# tf330.net
KiCad netlist of a schematic drawn in EAGLE
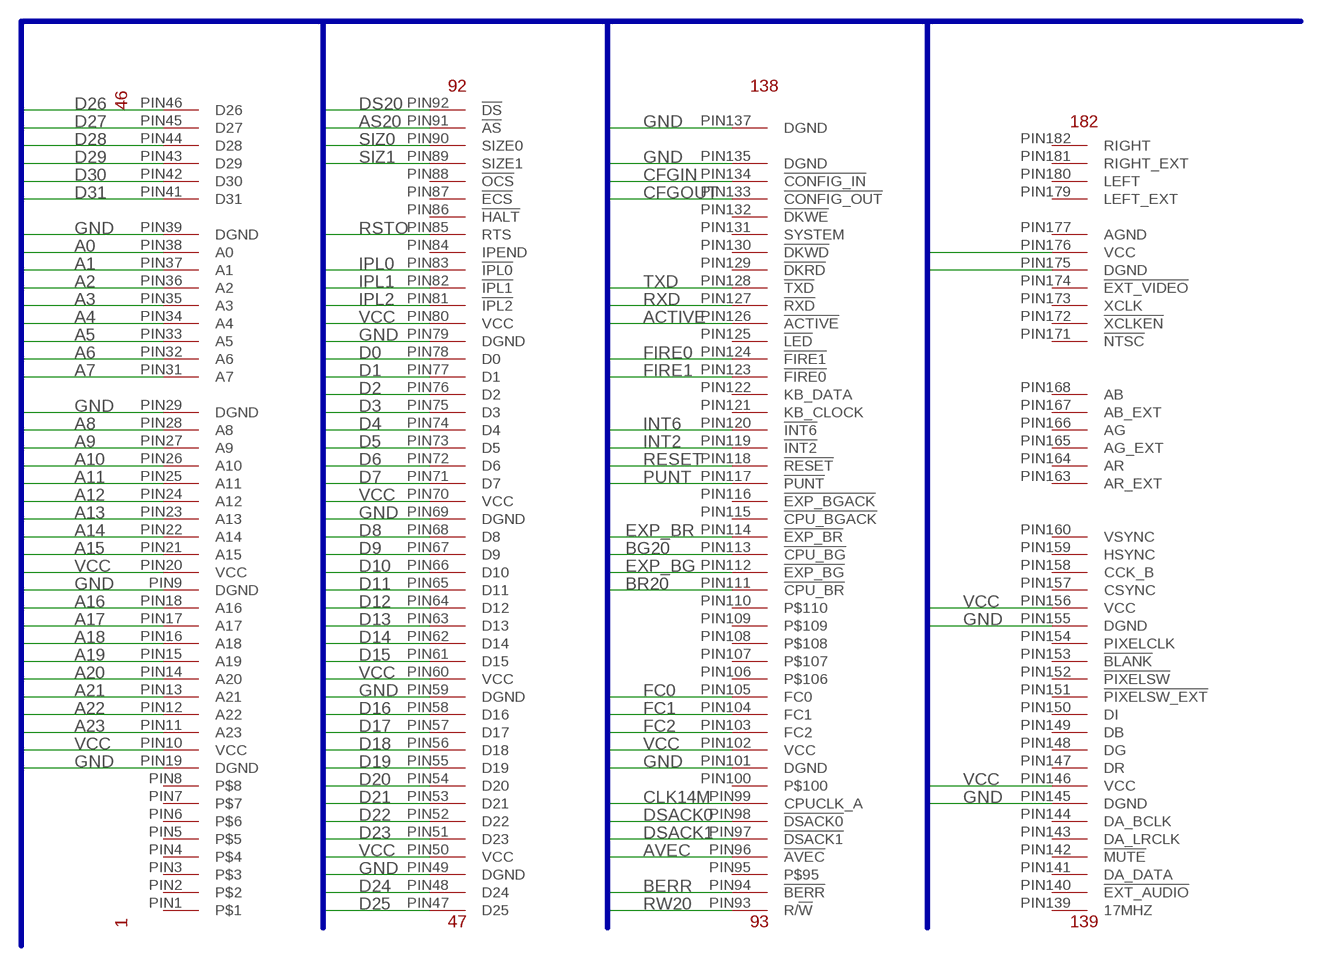
[diagram p0: schematic, sheet 1]
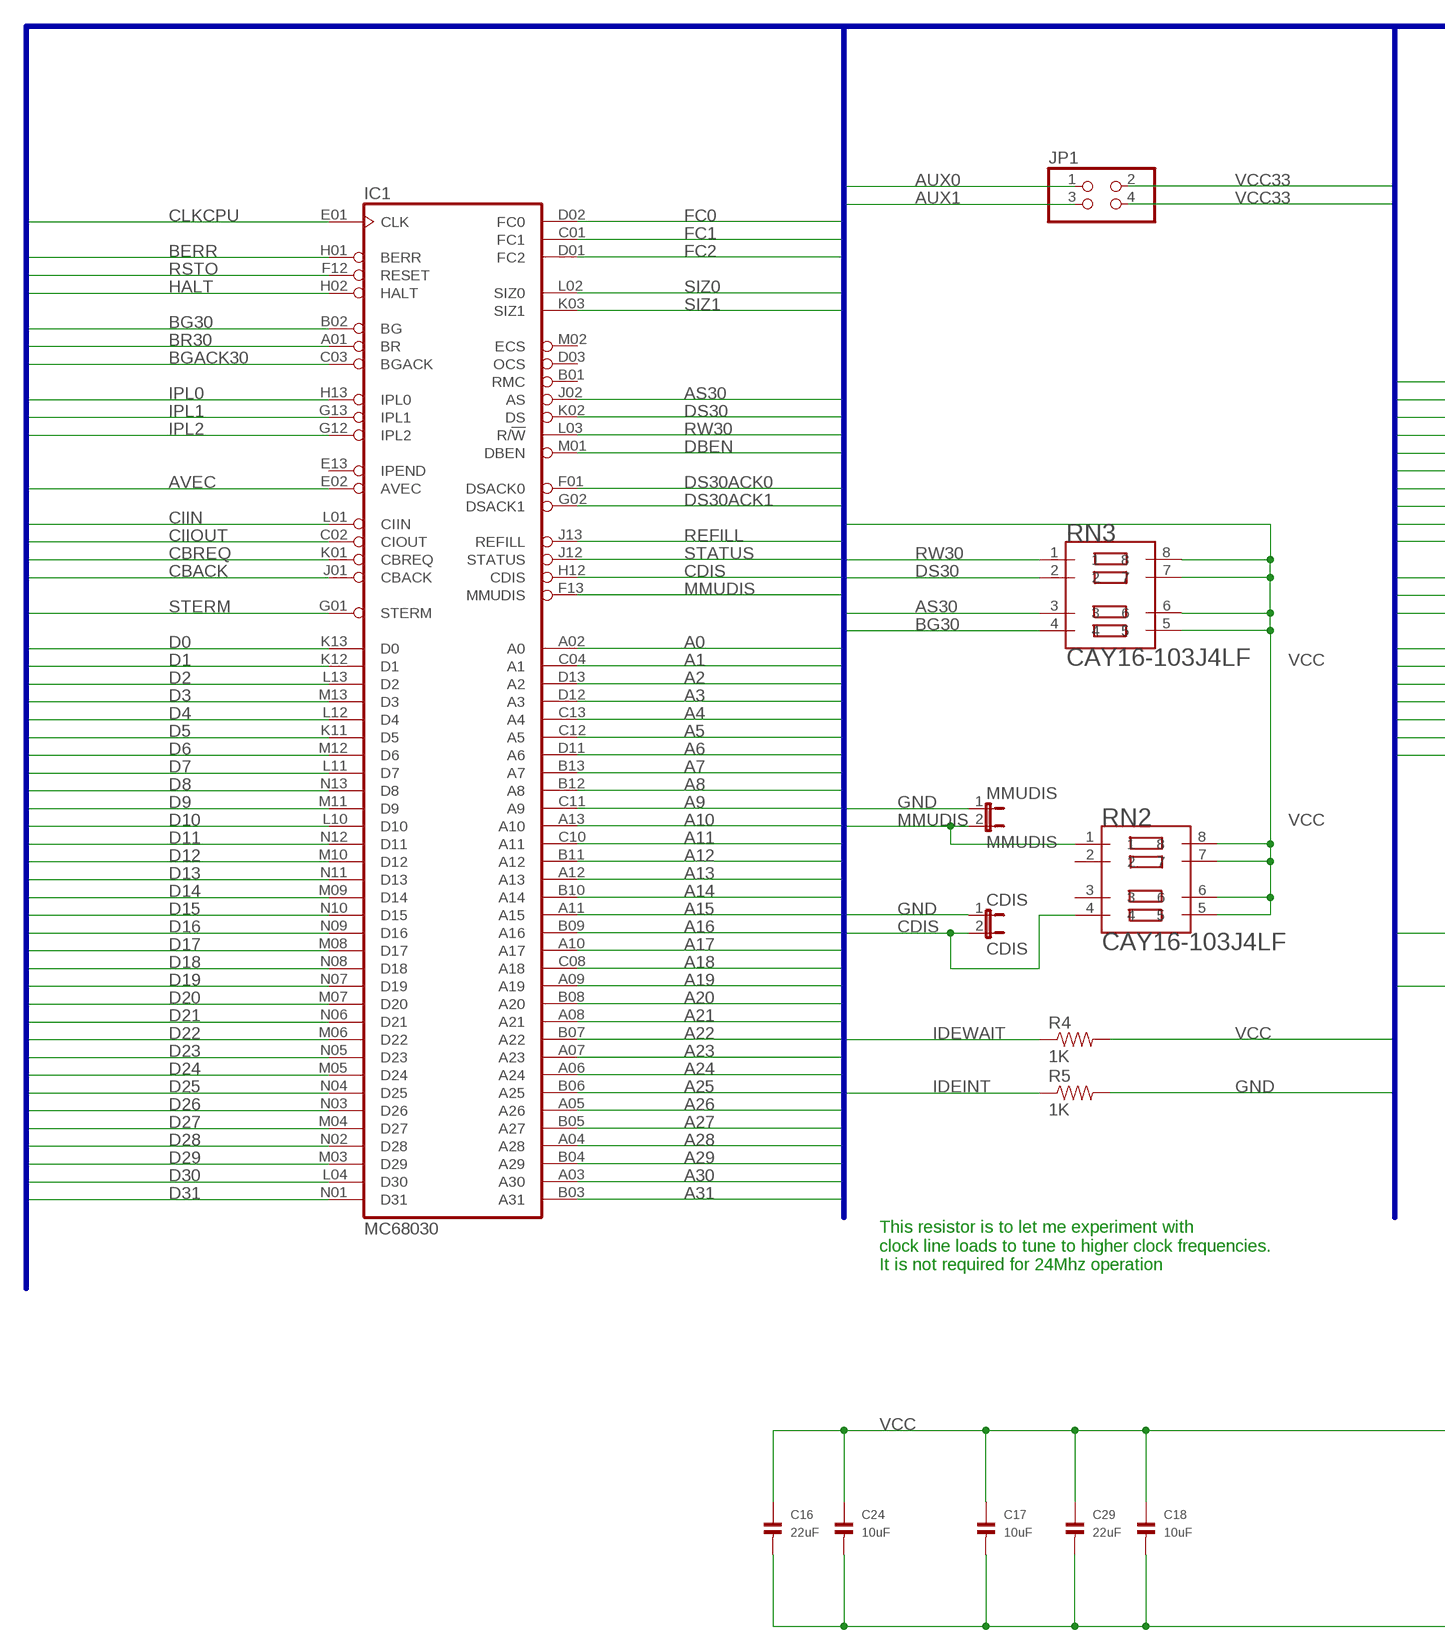
[diagram p1: schematic, sheet 2, part 1 of 2]
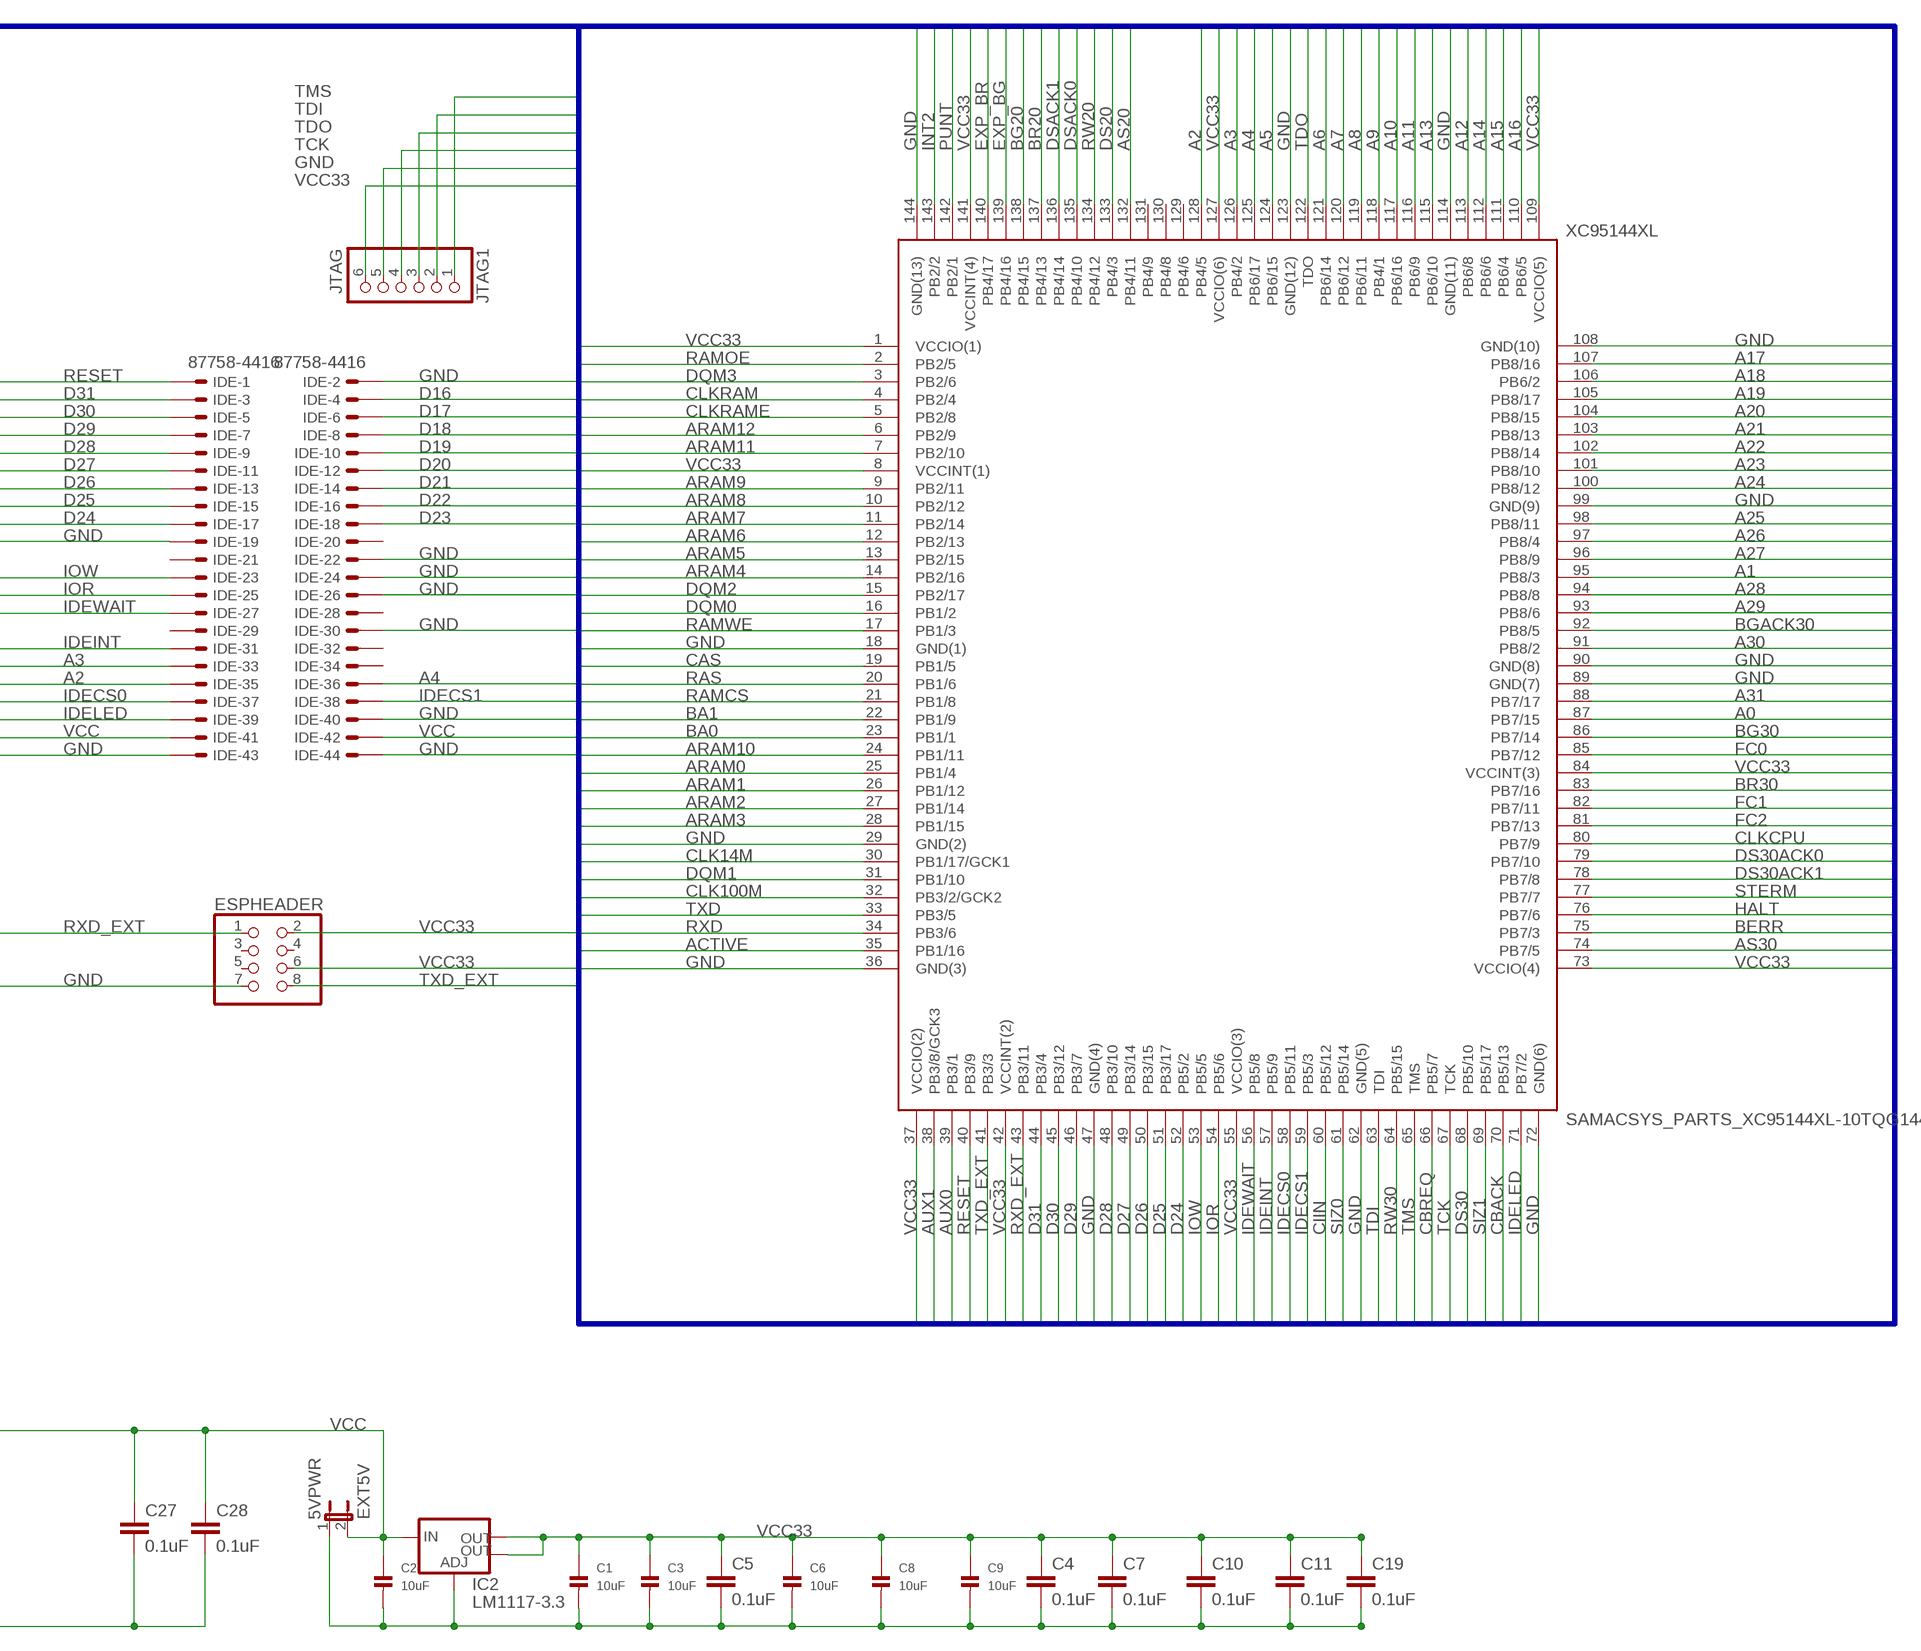
[diagram p2: schematic, sheet 2, part 2 of 2]
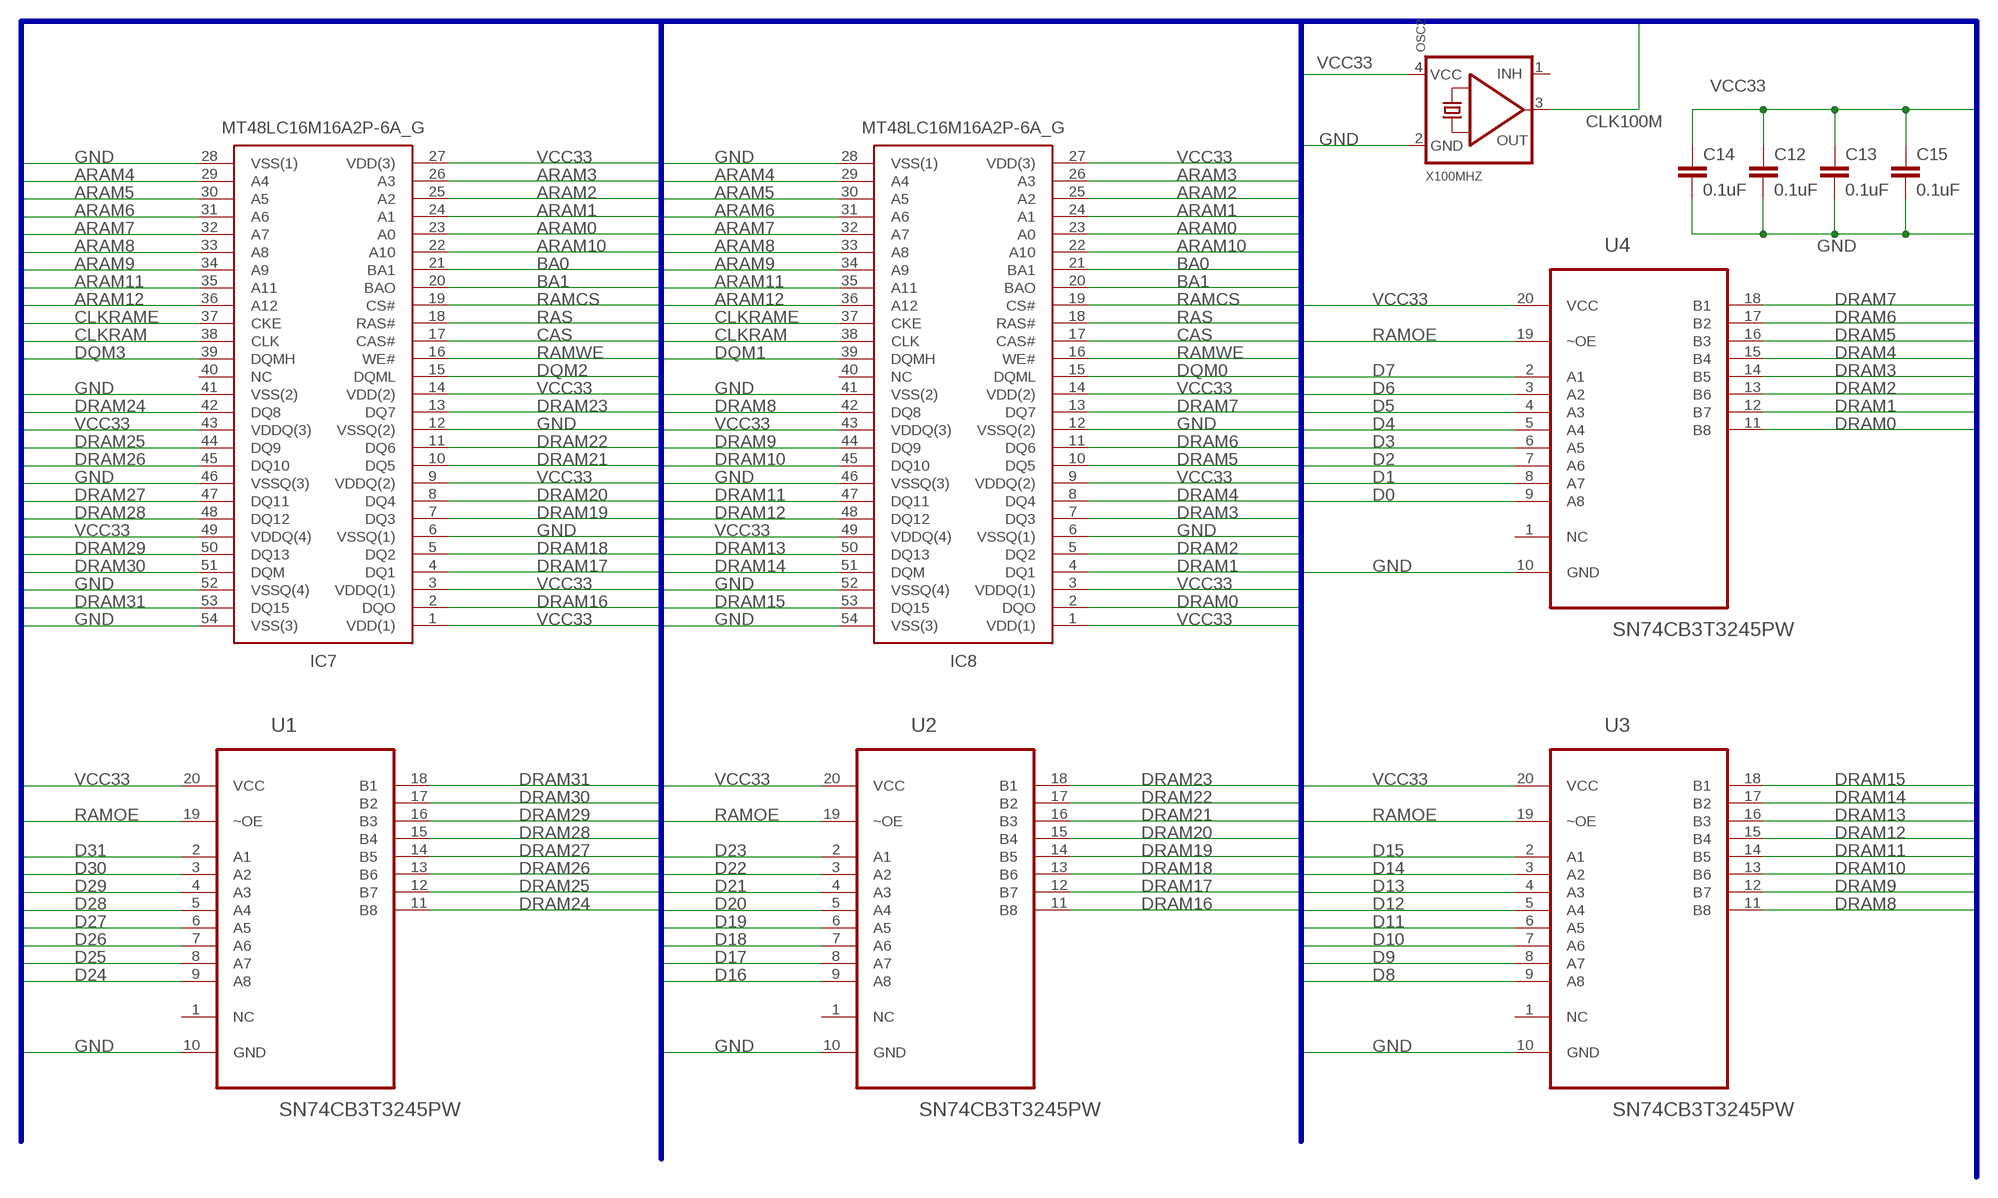
[diagram p3: schematic, sheet 3]

(export (version "E")
  (design (tool "Eeschema 10.0.6"))
  (components
    (comp (ref "CONN1")
      (value "MCA_CONN_182")
      (footprint "eagle-import:MCA_CONN_182")
      (libsource (lib "eagle-import") (part "MCA_CONN_182"))
    )
    (comp (ref "5VPWR")
      (value "EXT5V")
      (footprint "eagle-import:1X02")
      (libsource (lib "eagle-import") (part "JUMPER-2PTH"))
    )
    (comp (ref "C1")
      (value "10uF")
      (footprint "eagle-import:1206")
      (libsource (lib "eagle-import") (part "CAP_CERAMIC1206"))
    )
    (comp (ref "C2")
      (value "10uF")
      (footprint "eagle-import:1206")
      (libsource (lib "eagle-import") (part "CAP_CERAMIC1206"))
    )
    (comp (ref "C3")
      (value "10uF")
      (footprint "eagle-import:1206")
      (libsource (lib "eagle-import") (part "CAP_CERAMIC1206"))
    )
    (comp (ref "C4")
      (value "0.1uF")
      (footprint "eagle-import:0603-CAP")
      (libsource (lib "eagle-import") (part "0.1UF-25V(+80/-20%)(0603)"))
    )
    (comp (ref "C5")
      (value "0.1uF")
      (footprint "eagle-import:0603-CAP")
      (libsource (lib "eagle-import") (part "0.1UF-25V(+80/-20%)(0603)"))
    )
    (comp (ref "C6")
      (value "10uF")
      (footprint "eagle-import:1206")
      (libsource (lib "eagle-import") (part "CAP_CERAMIC1206"))
    )
    (comp (ref "C7")
      (value "0.1uF")
      (footprint "eagle-import:0603-CAP")
      (libsource (lib "eagle-import") (part "0.1UF-25V(+80/-20%)(0603)"))
    )
    (comp (ref "C8")
      (value "10uF")
      (footprint "eagle-import:1206")
      (libsource (lib "eagle-import") (part "CAP_CERAMIC1206"))
    )
    (comp (ref "C9")
      (value "10uF")
      (footprint "eagle-import:1206")
      (libsource (lib "eagle-import") (part "CAP_CERAMIC1206"))
    )
    (comp (ref "C10")
      (value "0.1uF")
      (footprint "eagle-import:0603-CAP")
      (libsource (lib "eagle-import") (part "0.1UF-25V(+80/-20%)(0603)"))
    )
    (comp (ref "C11")
      (value "0.1uF")
      (footprint "eagle-import:0603-CAP")
      (libsource (lib "eagle-import") (part "0.1UF-25V(+80/-20%)(0603)"))
    )
    (comp (ref "C16")
      (value "22uF")
      (footprint "eagle-import:1206")
      (libsource (lib "eagle-import") (part "CAP_CERAMIC1206"))
    )
    (comp (ref "C17")
      (value "10uF")
      (footprint "eagle-import:1206")
      (libsource (lib "eagle-import") (part "CAP_CERAMIC1206"))
    )
    (comp (ref "C18")
      (value "10uF")
      (footprint "eagle-import:1206")
      (libsource (lib "eagle-import") (part "CAP_CERAMIC1206"))
    )
    (comp (ref "C19")
      (value "0.1uF")
      (footprint "eagle-import:0603-CAP")
      (libsource (lib "eagle-import") (part "0.1UF-25V(+80/-20%)(0603)"))
    )
    (comp (ref "C24")
      (value "10uF")
      (footprint "eagle-import:1206")
      (libsource (lib "eagle-import") (part "CAP_CERAMIC1206"))
    )
    (comp (ref "C27")
      (value "0.1uF")
      (footprint "eagle-import:0603-CAP")
      (libsource (lib "eagle-import") (part "0.1UF-25V(+80/-20%)(0603)"))
    )
    (comp (ref "C28")
      (value "0.1uF")
      (footprint "eagle-import:0603-CAP")
      (libsource (lib "eagle-import") (part "0.1UF-25V(+80/-20%)(0603)"))
    )
    (comp (ref "C29")
      (value "22uF")
      (footprint "eagle-import:1206")
      (libsource (lib "eagle-import") (part "CAP_CERAMIC1206"))
    )
    (comp (ref "CDIS")
      (value "CDIS")
      (footprint "eagle-import:1X02")
      (libsource (lib "eagle-import") (part "JUMPER-2PTH"))
    )
    (comp (ref "ESPHEADER")
      (value "PINHD-2X4")
      (footprint "eagle-import:2X04")
      (libsource (lib "eagle-import") (part "PINHD-2X4"))
    )
    (comp (ref "IC1")
      (value "MC68030")
      (footprint "eagle-import:MPGA128")
      (fields (field (name "MF") "MOTOROLA") (field (name "MPN") "MC68030RC50C"))
      (libsource (lib "eagle-import") (part "MC68030RC"))
    )
    (comp (ref "IC2")
      (value "LM1117-3.3")
      (footprint "eagle-import:SOT223")
      (libsource (lib "eagle-import") (part "V_REG_LM1117SOT223"))
    )
    (comp (ref "IDE")
      (value "87758-4416")
      (footprint "eagle-import:87758-4416")
      (fields (field (name "MF") "MOLEX"))
      (libsource (lib "eagle-import") (part "87758-4416"))
    )
    (comp (ref "JP1")
      (value "PINHD-2X2")
      (footprint "eagle-import:2X02")
      (libsource (lib "eagle-import") (part "PINHD-2X2"))
    )
    (comp (ref "JTAG1")
      (value "JTAG")
      (footprint "eagle-import:1X06_ROUND")
      (libsource (lib "eagle-import") (part "HEADER-1X6ROUND"))
    )
    (comp (ref "MMUDIS")
      (value "MMUDIS")
      (footprint "eagle-import:1X02")
      (libsource (lib "eagle-import") (part "JUMPER-2PTH"))
    )
    (comp (ref "R4")
      (value "1K")
      (footprint "eagle-import:0603")
      (libsource (lib "eagle-import") (part "0.05OHM-1/5W-1%(0603)"))
    )
    (comp (ref "R5")
      (value "1K")
      (footprint "eagle-import:0603")
      (libsource (lib "eagle-import") (part "0.05OHM-1/5W-1%(0603)"))
    )
    (comp (ref "RN2")
      (value "CAY16-103J4LF")
      (footprint "eagle-import:RESCAXE80P320X160-8N")
      (fields (field (name "MF") "Bourns"))
      (libsource (lib "eagle-import") (part "CAY16-103J4LF"))
    )
    (comp (ref "RN3")
      (value "CAY16-103J4LF")
      (footprint "eagle-import:RESCAXE80P320X160-8N")
      (fields (field (name "MF") "Bourns"))
      (libsource (lib "eagle-import") (part "CAY16-103J4LF"))
    )
    (comp (ref "XC95144XL")
      (value "SAMACSYS_PARTS_XC95144XL-10TQG144I")
      (footprint "eagle-import:SAMACSYS_PARTS_QFP50P2200X2200X160-144N")
      (fields
        (field (name "MANUFACTURER_PART_NUMBER") "XC95144XL-10TQG144I")
        (field (name "RS_PART_NUMBER") "6260624")
      )
      (libsource (lib "eagle-import") (part "SAMACSYS_PARTS_XC95144XL-10TQG144I"))
    )
    (comp (ref "C12")
      (value "0.1uF")
      (footprint "eagle-import:0603-CAP")
      (libsource (lib "eagle-import") (part "0.1UF-25V(+80/-20%)(0603)"))
    )
    (comp (ref "C13")
      (value "0.1uF")
      (footprint "eagle-import:0603-CAP")
      (libsource (lib "eagle-import") (part "0.1UF-25V(+80/-20%)(0603)"))
    )
    (comp (ref "C14")
      (value "0.1uF")
      (footprint "eagle-import:0603-CAP")
      (libsource (lib "eagle-import") (part "0.1UF-25V(+80/-20%)(0603)"))
    )
    (comp (ref "C15")
      (value "0.1uF")
      (footprint "eagle-import:0603-CAP")
      (libsource (lib "eagle-import") (part "0.1UF-25V(+80/-20%)(0603)"))
    )
    (comp (ref "IC7")
      (value "MT48LC16M16A2P-6A_G")
      (footprint "eagle-import:SOP80P1176X120-54N")
      (fields
        (field (name "MANUFACTURER_PART_NUMBER") "MT48LC16M16A2P-6A:G")
        (field (name "RS_PART_NUMBER") "7824553")
      )
      (libsource (lib "eagle-import") (part "MT48LC16M16A2P-6A_G"))
    )
    (comp (ref "IC8")
      (value "MT48LC16M16A2P-6A_G")
      (footprint "eagle-import:SOP80P1176X120-54N")
      (fields
        (field (name "MANUFACTURER_PART_NUMBER") "MT48LC16M16A2P-6A:G")
        (field (name "RS_PART_NUMBER") "7824553")
      )
      (libsource (lib "eagle-import") (part "MT48LC16M16A2P-6A_G"))
    )
    (comp (ref "OSC2")
      (value "X100MHZ")
      (footprint "eagle-import:OSC_7X5MM")
      (libsource (lib "eagle-import") (part "OSCILLATOR"))
    )
    (comp (ref "U1")
      (value "SN74CB3T3245PW")
      (footprint "eagle-import:SOP65P640X120-20N")
      (fields (field (name "MF") "Texas Instruments"))
      (libsource (lib "eagle-import") (part "SN74CB3T3245PW"))
    )
    (comp (ref "U2")
      (value "SN74CB3T3245PW")
      (footprint "eagle-import:SOP65P640X120-20N")
      (fields (field (name "MF") "Texas Instruments"))
      (libsource (lib "eagle-import") (part "SN74CB3T3245PW"))
    )
    (comp (ref "U3")
      (value "SN74CB3T3245PW")
      (footprint "eagle-import:SOP65P640X120-20N")
      (fields (field (name "MF") "Texas Instruments"))
      (libsource (lib "eagle-import") (part "SN74CB3T3245PW"))
    )
    (comp (ref "U4")
      (value "SN74CB3T3245PW")
      (footprint "eagle-import:SOP65P640X120-20N")
      (fields (field (name "MF") "Texas Instruments"))
      (libsource (lib "eagle-import") (part "SN74CB3T3245PW"))
    )
  )
  (nets
    (net (code "11") (name "A0") (class "Default")
      (node (ref "CONN1") (pin "PIN38") (pinfunction "A0_PIN38") (pintype "bidirectional"))
      (node (ref "IC1") (pin "A02") (pinfunction "A0_A02") (pintype "output"))
      (node (ref "XC95144XL") (pin "87") (pinfunction "PB7/15_87") (pintype "input"))
    )
    (net (code "12") (name "A1") (class "Default")
      (node (ref "CONN1") (pin "PIN37") (pinfunction "A1_PIN37") (pintype "bidirectional"))
      (node (ref "IC1") (pin "C04") (pinfunction "A1_C04") (pintype "output"))
      (node (ref "XC95144XL") (pin "95") (pinfunction "PB8/3_95") (pintype "input"))
    )
    (net (code "13") (name "A2") (class "Default")
      (node (ref "CONN1") (pin "PIN36") (pinfunction "A2_PIN36") (pintype "bidirectional"))
      (node (ref "IC1") (pin "D13") (pinfunction "A2_D13") (pintype "output"))
      (node (ref "IDE") (pin "35") (pinfunction "S_35") (pintype "passive"))
      (node (ref "XC95144XL") (pin "128") (pinfunction "PB4/5_128") (pintype "input"))
    )
    (net (code "14") (name "A3") (class "Default")
      (node (ref "CONN1") (pin "PIN35") (pinfunction "A3_PIN35") (pintype "bidirectional"))
      (node (ref "IC1") (pin "D12") (pinfunction "A3_D12") (pintype "output"))
      (node (ref "IDE") (pin "33") (pinfunction "S_33") (pintype "passive"))
      (node (ref "XC95144XL") (pin "126") (pinfunction "PB4/2_126") (pintype "input"))
    )
    (net (code "15") (name "A4") (class "Default")
      (node (ref "CONN1") (pin "PIN34") (pinfunction "A4_PIN34") (pintype "bidirectional"))
      (node (ref "IC1") (pin "C13") (pinfunction "A4_C13") (pintype "output"))
      (node (ref "IDE") (pin "36") (pinfunction "S_36") (pintype "passive"))
      (node (ref "XC95144XL") (pin "125") (pinfunction "PB6/17_125") (pintype "input"))
    )
    (net (code "16") (name "A5") (class "Default")
      (node (ref "CONN1") (pin "PIN33") (pinfunction "A5_PIN33") (pintype "bidirectional"))
      (node (ref "IC1") (pin "C12") (pinfunction "A5_C12") (pintype "output"))
      (node (ref "XC95144XL") (pin "124") (pinfunction "PB6/15_124") (pintype "input"))
    )
    (net (code "17") (name "A6") (class "Default")
      (node (ref "CONN1") (pin "PIN32") (pinfunction "A6_PIN32") (pintype "bidirectional"))
      (node (ref "IC1") (pin "D11") (pinfunction "A6_D11") (pintype "output"))
      (node (ref "XC95144XL") (pin "121") (pinfunction "PB6/14_121") (pintype "input"))
    )
    (net (code "18") (name "A7") (class "Default")
      (node (ref "CONN1") (pin "PIN31") (pinfunction "A7_PIN31") (pintype "bidirectional"))
      (node (ref "IC1") (pin "B13") (pinfunction "A7_B13") (pintype "output"))
      (node (ref "XC95144XL") (pin "120") (pinfunction "PB6/12_120") (pintype "input"))
    )
    (net (code "19") (name "A8") (class "Default")
      (node (ref "CONN1") (pin "PIN28") (pinfunction "A8_PIN28") (pintype "bidirectional"))
      (node (ref "IC1") (pin "B12") (pinfunction "A8_B12") (pintype "output"))
      (node (ref "XC95144XL") (pin "119") (pinfunction "PB6/11_119") (pintype "input"))
    )
    (net (code "20") (name "A9") (class "Default")
      (node (ref "CONN1") (pin "PIN27") (pinfunction "A9_PIN27") (pintype "bidirectional"))
      (node (ref "IC1") (pin "C11") (pinfunction "A9_C11") (pintype "output"))
      (node (ref "XC95144XL") (pin "118") (pinfunction "PB4/1_118") (pintype "input"))
    )
    (net (code "21") (name "A10") (class "Default")
      (node (ref "CONN1") (pin "PIN26") (pinfunction "A10_PIN26") (pintype "bidirectional"))
      (node (ref "IC1") (pin "A13") (pinfunction "A10_A13") (pintype "output"))
      (node (ref "XC95144XL") (pin "117") (pinfunction "PB6/16_117") (pintype "input"))
    )
    (net (code "22") (name "A11") (class "Default")
      (node (ref "CONN1") (pin "PIN25") (pinfunction "A11_PIN25") (pintype "bidirectional"))
      (node (ref "IC1") (pin "C10") (pinfunction "A11_C10") (pintype "output"))
      (node (ref "XC95144XL") (pin "116") (pinfunction "PB6/9_116") (pintype "input"))
    )
    (net (code "23") (name "A12") (class "Default")
      (node (ref "CONN1") (pin "PIN24") (pinfunction "A12_PIN24") (pintype "bidirectional"))
      (node (ref "IC1") (pin "B11") (pinfunction "A12_B11") (pintype "output"))
      (node (ref "XC95144XL") (pin "113") (pinfunction "PB6/8_113") (pintype "input"))
    )
    (net (code "24") (name "A13") (class "Default")
      (node (ref "CONN1") (pin "PIN23") (pinfunction "A13_PIN23") (pintype "bidirectional"))
      (node (ref "IC1") (pin "A12") (pinfunction "A13_A12") (pintype "output"))
      (node (ref "XC95144XL") (pin "115") (pinfunction "PB6/10_115") (pintype "input"))
    )
    (net (code "25") (name "A14") (class "Default")
      (node (ref "CONN1") (pin "PIN22") (pinfunction "A14_PIN22") (pintype "bidirectional"))
      (node (ref "IC1") (pin "B10") (pinfunction "A14_B10") (pintype "output"))
      (node (ref "XC95144XL") (pin "112") (pinfunction "PB6/6_112") (pintype "input"))
    )
    (net (code "26") (name "A15") (class "Default")
      (node (ref "CONN1") (pin "PIN21") (pinfunction "A15_PIN21") (pintype "bidirectional"))
      (node (ref "IC1") (pin "A11") (pinfunction "A15_A11") (pintype "output"))
      (node (ref "XC95144XL") (pin "111") (pinfunction "PB6/4_111") (pintype "input"))
    )
    (net (code "27") (name "A16") (class "Default")
      (node (ref "CONN1") (pin "PIN18") (pinfunction "A16_PIN18") (pintype "bidirectional"))
      (node (ref "IC1") (pin "B09") (pinfunction "A16_B09") (pintype "output"))
      (node (ref "XC95144XL") (pin "110") (pinfunction "PB6/5_110") (pintype "input"))
    )
    (net (code "28") (name "A17") (class "Default")
      (node (ref "CONN1") (pin "PIN17") (pinfunction "A17_PIN17") (pintype "bidirectional"))
      (node (ref "IC1") (pin "A10") (pinfunction "A17_A10") (pintype "output"))
      (node (ref "XC95144XL") (pin "107") (pinfunction "PB8/16_107") (pintype "input"))
    )
    (net (code "29") (name "A18") (class "Default")
      (node (ref "CONN1") (pin "PIN16") (pinfunction "A18_PIN16") (pintype "bidirectional"))
      (node (ref "IC1") (pin "C08") (pinfunction "A18_C08") (pintype "output"))
      (node (ref "XC95144XL") (pin "106") (pinfunction "PB6/2_106") (pintype "input"))
    )
    (net (code "30") (name "A19") (class "Default")
      (node (ref "CONN1") (pin "PIN15") (pinfunction "A19_PIN15") (pintype "bidirectional"))
      (node (ref "IC1") (pin "A09") (pinfunction "A19_A09") (pintype "output"))
      (node (ref "XC95144XL") (pin "105") (pinfunction "PB8/17_105") (pintype "input"))
    )
    (net (code "31") (name "A20") (class "Default")
      (node (ref "CONN1") (pin "PIN14") (pinfunction "A20_PIN14") (pintype "bidirectional"))
      (node (ref "IC1") (pin "B08") (pinfunction "A20_B08") (pintype "output"))
      (node (ref "XC95144XL") (pin "104") (pinfunction "PB8/15_104") (pintype "input"))
    )
    (net (code "32") (name "A21") (class "Default")
      (node (ref "CONN1") (pin "PIN13") (pinfunction "A21_PIN13") (pintype "bidirectional"))
      (node (ref "IC1") (pin "A08") (pinfunction "A21_A08") (pintype "output"))
      (node (ref "XC95144XL") (pin "103") (pinfunction "PB8/13_103") (pintype "input"))
    )
    (net (code "33") (name "A22") (class "Default")
      (node (ref "CONN1") (pin "PIN12") (pinfunction "A22_PIN12") (pintype "bidirectional"))
      (node (ref "IC1") (pin "B07") (pinfunction "A22_B07") (pintype "output"))
      (node (ref "XC95144XL") (pin "102") (pinfunction "PB8/14_102") (pintype "input"))
    )
    (net (code "34") (name "A23") (class "Default")
      (node (ref "CONN1") (pin "PIN11") (pinfunction "A23_PIN11") (pintype "bidirectional"))
      (node (ref "IC1") (pin "A07") (pinfunction "A23_A07") (pintype "output"))
      (node (ref "XC95144XL") (pin "101") (pinfunction "PB8/10_101") (pintype "input"))
    )
    (net (code "35") (name "A24") (class "Default")
      (node (ref "IC1") (pin "A06") (pinfunction "A24_A06") (pintype "output"))
      (node (ref "XC95144XL") (pin "100") (pinfunction "PB8/12_100") (pintype "input"))
    )
    (net (code "36") (name "A25") (class "Default")
      (node (ref "IC1") (pin "B06") (pinfunction "A25_B06") (pintype "output"))
      (node (ref "XC95144XL") (pin "98") (pinfunction "PB8/11_98") (pintype "input"))
    )
    (net (code "37") (name "A26") (class "Default")
      (node (ref "IC1") (pin "A05") (pinfunction "A26_A05") (pintype "output"))
      (node (ref "XC95144XL") (pin "97") (pinfunction "PB8/4_97") (pintype "input"))
    )
    (net (code "38") (name "A27") (class "Default")
      (node (ref "IC1") (pin "B05") (pinfunction "A27_B05") (pintype "output"))
      (node (ref "XC95144XL") (pin "96") (pinfunction "PB8/9_96") (pintype "input"))
    )
    (net (code "39") (name "A28") (class "Default")
      (node (ref "IC1") (pin "A04") (pinfunction "A28_A04") (pintype "output"))
      (node (ref "XC95144XL") (pin "94") (pinfunction "PB8/8_94") (pintype "input"))
    )
    (net (code "40") (name "A29") (class "Default")
      (node (ref "IC1") (pin "B04") (pinfunction "A29_B04") (pintype "output"))
      (node (ref "XC95144XL") (pin "93") (pinfunction "PB8/6_93") (pintype "input"))
    )
    (net (code "41") (name "A30") (class "Default")
      (node (ref "IC1") (pin "A03") (pinfunction "A30_A03") (pintype "output"))
      (node (ref "XC95144XL") (pin "91") (pinfunction "PB8/2_91") (pintype "input"))
    )
    (net (code "42") (name "A31") (class "Default")
      (node (ref "IC1") (pin "B03") (pinfunction "A31_B03") (pintype "output"))
      (node (ref "XC95144XL") (pin "88") (pinfunction "PB7/17_88") (pintype "input"))
    )
    (net (code "43") (name "ACTIVE") (class "Default")
      (node (ref "CONN1") (pin "PIN126") (pinfunction "~{ACTIVE}_PIN126") (pintype "bidirectional"))
      (node (ref "XC95144XL") (pin "35") (pinfunction "PB1/16_35") (pintype "input"))
    )
    (net (code "44") (name "AGND") (class "Default")
      (node (ref "CONN1") (pin "PIN177") (pinfunction "AGND_PIN177") (pintype "power_in"))
    )
    (net (code "45") (name "ARAM0") (class "Default")
      (node (ref "IC7") (pin "23") (pinfunction "A0_23") (pintype "input"))
      (node (ref "IC8") (pin "23") (pinfunction "A0_23") (pintype "input"))
      (node (ref "XC95144XL") (pin "25") (pinfunction "PB1/4_25") (pintype "input"))
    )
    (net (code "46") (name "ARAM1") (class "Default")
      (node (ref "IC7") (pin "24") (pinfunction "A1_24") (pintype "input"))
      (node (ref "IC8") (pin "24") (pinfunction "A1_24") (pintype "input"))
      (node (ref "XC95144XL") (pin "26") (pinfunction "PB1/12_26") (pintype "input"))
    )
    (net (code "47") (name "ARAM2") (class "Default")
      (node (ref "IC7") (pin "25") (pinfunction "A2_25") (pintype "input"))
      (node (ref "IC8") (pin "25") (pinfunction "A2_25") (pintype "input"))
      (node (ref "XC95144XL") (pin "27") (pinfunction "PB1/14_27") (pintype "input"))
    )
    (net (code "48") (name "ARAM3") (class "Default")
      (node (ref "IC7") (pin "26") (pinfunction "A3_26") (pintype "input"))
      (node (ref "IC8") (pin "26") (pinfunction "A3_26") (pintype "input"))
      (node (ref "XC95144XL") (pin "28") (pinfunction "PB1/15_28") (pintype "input"))
    )
    (net (code "49") (name "ARAM4") (class "Default")
      (node (ref "IC7") (pin "29") (pinfunction "A4_29") (pintype "input"))
      (node (ref "IC8") (pin "29") (pinfunction "A4_29") (pintype "input"))
      (node (ref "XC95144XL") (pin "14") (pinfunction "PB2/16_14") (pintype "input"))
    )
    (net (code "50") (name "ARAM5") (class "Default")
      (node (ref "IC7") (pin "30") (pinfunction "A5_30") (pintype "input"))
      (node (ref "IC8") (pin "30") (pinfunction "A5_30") (pintype "input"))
      (node (ref "XC95144XL") (pin "13") (pinfunction "PB2/15_13") (pintype "input"))
    )
    (net (code "51") (name "ARAM6") (class "Default")
      (node (ref "IC7") (pin "31") (pinfunction "A6_31") (pintype "input"))
      (node (ref "IC8") (pin "31") (pinfunction "A6_31") (pintype "input"))
      (node (ref "XC95144XL") (pin "12") (pinfunction "PB2/13_12") (pintype "input"))
    )
    (net (code "52") (name "ARAM7") (class "Default")
      (node (ref "IC7") (pin "32") (pinfunction "A7_32") (pintype "input"))
      (node (ref "IC8") (pin "32") (pinfunction "A7_32") (pintype "input"))
      (node (ref "XC95144XL") (pin "11") (pinfunction "PB2/14_11") (pintype "input"))
    )
    (net (code "53") (name "ARAM8") (class "Default")
      (node (ref "IC7") (pin "33") (pinfunction "A8_33") (pintype "input"))
      (node (ref "IC8") (pin "33") (pinfunction "A8_33") (pintype "input"))
      (node (ref "XC95144XL") (pin "10") (pinfunction "PB2/12_10") (pintype "input"))
    )
    (net (code "54") (name "ARAM9") (class "Default")
      (node (ref "IC7") (pin "34") (pinfunction "A9_34") (pintype "input"))
      (node (ref "IC8") (pin "34") (pinfunction "A9_34") (pintype "input"))
      (node (ref "XC95144XL") (pin "9") (pinfunction "PB2/11_9") (pintype "input"))
    )
    (net (code "55") (name "ARAM10") (class "Default")
      (node (ref "IC7") (pin "22") (pinfunction "A10_22") (pintype "input"))
      (node (ref "IC8") (pin "22") (pinfunction "A10_22") (pintype "input"))
      (node (ref "XC95144XL") (pin "24") (pinfunction "PB1/11_24") (pintype "input"))
    )
    (net (code "56") (name "ARAM11") (class "Default")
      (node (ref "IC7") (pin "35") (pinfunction "A11_35") (pintype "input"))
      (node (ref "IC8") (pin "35") (pinfunction "A11_35") (pintype "input"))
      (node (ref "XC95144XL") (pin "7") (pinfunction "PB2/10_7") (pintype "input"))
    )
    (net (code "57") (name "ARAM12") (class "Default")
      (node (ref "IC7") (pin "36") (pinfunction "A12_36") (pintype "input"))
      (node (ref "IC8") (pin "36") (pinfunction "A12_36") (pintype "input"))
      (node (ref "XC95144XL") (pin "6") (pinfunction "PB2/9_6") (pintype "input"))
    )
    (net (code "58") (name "AS20") (class "Default")
      (node (ref "CONN1") (pin "PIN91") (pinfunction "~{AS}_PIN91") (pintype "bidirectional"))
      (node (ref "XC95144XL") (pin "132") (pinfunction "PB4/11_132") (pintype "input"))
    )
    (net (code "59") (name "AS30") (class "Default")
      (node (ref "IC1") (pin "J02") (pinfunction "AS_J02") (pintype "output"))
      (node (ref "RN3") (pin "3") (pinfunction "3_3") (pintype "passive"))
      (node (ref "XC95144XL") (pin "74") (pinfunction "PB7/5_74") (pintype "input"))
    )
    (net (code "60") (name "AUX0") (class "Default")
      (node (ref "JP1") (pin "1") (pinfunction "1_1") (pintype "passive"))
      (node (ref "XC95144XL") (pin "39") (pinfunction "PB3/1_39") (pintype "input"))
    )
    (net (code "61") (name "AUX1") (class "Default")
      (node (ref "JP1") (pin "3") (pinfunction "3_3") (pintype "passive"))
      (node (ref "XC95144XL") (pin "38") (pinfunction "PB3/8/GCK3_38") (pintype "input"))
    )
    (net (code "62") (name "AVEC") (class "Default")
      (node (ref "CONN1") (pin "PIN96") (pinfunction "~{AVEC}_PIN96") (pintype "bidirectional"))
      (node (ref "IC1") (pin "E02") (pinfunction "AVEC_E02") (pintype "input"))
    )
    (net (code "63") (name "BA0") (class "Default")
      (node (ref "IC7") (pin "21") (pinfunction "BA1_21") (pintype "input"))
      (node (ref "IC8") (pin "21") (pinfunction "BA1_21") (pintype "input"))
      (node (ref "XC95144XL") (pin "23") (pinfunction "PB1/1_23") (pintype "input"))
    )
    (net (code "64") (name "BA1") (class "Default")
      (node (ref "IC7") (pin "20") (pinfunction "BAO_20") (pintype "input"))
      (node (ref "IC8") (pin "20") (pinfunction "BAO_20") (pintype "input"))
      (node (ref "XC95144XL") (pin "22") (pinfunction "PB1/9_22") (pintype "input"))
    )
    (net (code "65") (name "BERR") (class "Default")
      (node (ref "CONN1") (pin "PIN94") (pinfunction "~{BERR}_PIN94") (pintype "bidirectional"))
      (node (ref "IC1") (pin "H01") (pinfunction "BERR_H01") (pintype "input"))
      (node (ref "XC95144XL") (pin "75") (pinfunction "PB7/3_75") (pintype "input"))
    )
    (net (code "66") (name "BG20") (class "Default")
      (node (ref "CONN1") (pin "PIN113") (pinfunction "~{CPU_BG}_PIN113") (pintype "bidirectional"))
      (node (ref "XC95144XL") (pin "138") (pinfunction "PB4/15_138") (pintype "input"))
    )
    (net (code "67") (name "BG30") (class "Default")
      (node (ref "IC1") (pin "B02") (pinfunction "BG_B02") (pintype "output"))
      (node (ref "RN3") (pin "4") (pinfunction "4_4") (pintype "passive"))
      (node (ref "XC95144XL") (pin "86") (pinfunction "PB7/14_86") (pintype "input"))
    )
    (net (code "68") (name "BGACK30") (class "Default")
      (node (ref "IC1") (pin "C03") (pinfunction "BGACK_C03") (pintype "input"))
      (node (ref "XC95144XL") (pin "92") (pinfunction "PB8/5_92") (pintype "input"))
    )
    (net (code "69") (name "BR20") (class "Default")
      (node (ref "CONN1") (pin "PIN111") (pinfunction "~{CPU_BR}_PIN111") (pintype "bidirectional"))
      (node (ref "XC95144XL") (pin "137") (pinfunction "PB4/13_137") (pintype "input"))
    )
    (net (code "70") (name "BR30") (class "Default")
      (node (ref "IC1") (pin "A01") (pinfunction "BR_A01") (pintype "input"))
      (node (ref "XC95144XL") (pin "83") (pinfunction "PB7/16_83") (pintype "input"))
    )
    (net (code "71") (name "CAS") (class "Default")
      (node (ref "IC7") (pin "17") (pinfunction "CAS#_17") (pintype "input"))
      (node (ref "IC8") (pin "17") (pinfunction "CAS#_17") (pintype "input"))
      (node (ref "XC95144XL") (pin "19") (pinfunction "PB1/5_19") (pintype "input"))
    )
    (net (code "72") (name "CBACK") (class "Default")
      (node (ref "IC1") (pin "J01") (pinfunction "CBACK_J01") (pintype "input"))
      (node (ref "XC95144XL") (pin "70") (pinfunction "PB5/13_70") (pintype "input"))
    )
    (net (code "73") (name "CBREQ") (class "Default")
      (node (ref "IC1") (pin "K01") (pinfunction "CBREQ_K01") (pintype "output"))
      (node (ref "XC95144XL") (pin "66") (pinfunction "PB5/7_66") (pintype "input"))
    )
    (net (code "74") (name "CDIS") (class "Default")
      (node (ref "CDIS") (pin "2") (pinfunction "2_2") (pintype "passive"))
      (node (ref "IC1") (pin "H12") (pinfunction "CDIS_H12") (pintype "input"))
      (node (ref "RN2") (pin "4") (pinfunction "4_4") (pintype "passive"))
    )
    (net (code "75") (name "CFGIN") (class "Default")
      (node (ref "CONN1") (pin "PIN134") (pinfunction "~{CONFIG_IN}_PIN134") (pintype "bidirectional"))
    )
    (net (code "76") (name "CFGOUT") (class "Default")
      (node (ref "CONN1") (pin "PIN133") (pinfunction "~{CONFIG_OUT}_PIN133") (pintype "bidirectional"))
    )
    (net (code "77") (name "CIIN") (class "Default")
      (node (ref "IC1") (pin "L01") (pinfunction "CIIN_L01") (pintype "input"))
      (node (ref "XC95144XL") (pin "60") (pinfunction "PB5/12_60") (pintype "input"))
    )
    (net (code "78") (name "CIIOUT") (class "Default")
      (node (ref "IC1") (pin "C02") (pinfunction "CIOUT_C02") (pintype "output"))
    )
    (net (code "79") (name "CLK14M") (class "Default")
      (node (ref "CONN1") (pin "PIN99") (pinfunction "CPUCLK_A_PIN99") (pintype "bidirectional"))
      (node (ref "XC95144XL") (pin "30") (pinfunction "PB1/17/GCK1_30") (pintype "input"))
    )
    (net (code "80") (name "CLK100M") (class "Default")
      (node (ref "OSC2") (pin "3") (pinfunction "OUT_3") (pintype "output"))
      (node (ref "XC95144XL") (pin "32") (pinfunction "PB3/2/GCK2_32") (pintype "input"))
    )
    (net (code "81") (name "CLKCPU") (class "Default")
      (node (ref "IC1") (pin "E01") (pinfunction "CLK_E01") (pintype "input"))
      (node (ref "XC95144XL") (pin "80") (pinfunction "PB7/9_80") (pintype "input"))
    )
    (net (code "82") (name "CLKRAM") (class "Default")
      (node (ref "IC7") (pin "38") (pinfunction "CLK_38") (pintype "input"))
      (node (ref "IC8") (pin "38") (pinfunction "CLK_38") (pintype "input"))
      (node (ref "XC95144XL") (pin "4") (pinfunction "PB2/4_4") (pintype "input"))
    )
    (net (code "83") (name "CLKRAME") (class "Default")
      (node (ref "IC7") (pin "37") (pinfunction "CKE_37") (pintype "input"))
      (node (ref "IC8") (pin "37") (pinfunction "CKE_37") (pintype "input"))
      (node (ref "XC95144XL") (pin "5") (pinfunction "PB2/8_5") (pintype "input"))
    )
    (net (code "84") (name "D0") (class "Default")
      (node (ref "CONN1") (pin "PIN78") (pinfunction "D0_PIN78") (pintype "bidirectional"))
      (node (ref "IC1") (pin "K13") (pinfunction "D0_K13") (pintype "bidirectional"))
      (node (ref "U4") (pin "9") (pinfunction "A8_9") (pintype "bidirectional"))
    )
    (net (code "85") (name "D1") (class "Default")
      (node (ref "CONN1") (pin "PIN77") (pinfunction "D1_PIN77") (pintype "bidirectional"))
      (node (ref "IC1") (pin "K12") (pinfunction "D1_K12") (pintype "bidirectional"))
      (node (ref "U4") (pin "8") (pinfunction "A7_8") (pintype "bidirectional"))
    )
    (net (code "86") (name "D2") (class "Default")
      (node (ref "CONN1") (pin "PIN76") (pinfunction "D2_PIN76") (pintype "bidirectional"))
      (node (ref "IC1") (pin "L13") (pinfunction "D2_L13") (pintype "bidirectional"))
      (node (ref "U4") (pin "7") (pinfunction "A6_7") (pintype "bidirectional"))
    )
    (net (code "87") (name "D3") (class "Default")
      (node (ref "CONN1") (pin "PIN75") (pinfunction "D3_PIN75") (pintype "bidirectional"))
      (node (ref "IC1") (pin "M13") (pinfunction "D3_M13") (pintype "bidirectional"))
      (node (ref "U4") (pin "6") (pinfunction "A5_6") (pintype "bidirectional"))
    )
    (net (code "88") (name "D4") (class "Default")
      (node (ref "CONN1") (pin "PIN74") (pinfunction "D4_PIN74") (pintype "bidirectional"))
      (node (ref "IC1") (pin "L12") (pinfunction "D4_L12") (pintype "bidirectional"))
      (node (ref "U4") (pin "5") (pinfunction "A4_5") (pintype "bidirectional"))
    )
    (net (code "89") (name "D5") (class "Default")
      (node (ref "CONN1") (pin "PIN73") (pinfunction "D5_PIN73") (pintype "bidirectional"))
      (node (ref "IC1") (pin "K11") (pinfunction "D5_K11") (pintype "bidirectional"))
      (node (ref "U4") (pin "4") (pinfunction "A3_4") (pintype "bidirectional"))
    )
    (net (code "90") (name "D6") (class "Default")
      (node (ref "CONN1") (pin "PIN72") (pinfunction "D6_PIN72") (pintype "bidirectional"))
      (node (ref "IC1") (pin "M12") (pinfunction "D6_M12") (pintype "bidirectional"))
      (node (ref "U4") (pin "3") (pinfunction "A2_3") (pintype "bidirectional"))
    )
    (net (code "91") (name "D7") (class "Default")
      (node (ref "CONN1") (pin "PIN71") (pinfunction "D7_PIN71") (pintype "bidirectional"))
      (node (ref "IC1") (pin "L11") (pinfunction "D7_L11") (pintype "bidirectional"))
      (node (ref "U4") (pin "2") (pinfunction "A1_2") (pintype "bidirectional"))
    )
    (net (code "92") (name "D8") (class "Default")
      (node (ref "CONN1") (pin "PIN68") (pinfunction "D8_PIN68") (pintype "bidirectional"))
      (node (ref "IC1") (pin "N13") (pinfunction "D8_N13") (pintype "bidirectional"))
      (node (ref "U3") (pin "9") (pinfunction "A8_9") (pintype "bidirectional"))
    )
    (net (code "93") (name "D9") (class "Default")
      (node (ref "CONN1") (pin "PIN67") (pinfunction "D9_PIN67") (pintype "bidirectional"))
      (node (ref "IC1") (pin "M11") (pinfunction "D9_M11") (pintype "bidirectional"))
      (node (ref "U3") (pin "8") (pinfunction "A7_8") (pintype "bidirectional"))
    )
    (net (code "94") (name "D10") (class "Default")
      (node (ref "CONN1") (pin "PIN66") (pinfunction "D10_PIN66") (pintype "bidirectional"))
      (node (ref "IC1") (pin "L10") (pinfunction "D10_L10") (pintype "bidirectional"))
      (node (ref "U3") (pin "7") (pinfunction "A6_7") (pintype "bidirectional"))
    )
    (net (code "95") (name "D11") (class "Default")
      (node (ref "CONN1") (pin "PIN65") (pinfunction "D11_PIN65") (pintype "bidirectional"))
      (node (ref "IC1") (pin "N12") (pinfunction "D11_N12") (pintype "bidirectional"))
      (node (ref "U3") (pin "6") (pinfunction "A5_6") (pintype "bidirectional"))
    )
    (net (code "96") (name "D12") (class "Default")
      (node (ref "CONN1") (pin "PIN64") (pinfunction "D12_PIN64") (pintype "bidirectional"))
      (node (ref "IC1") (pin "M10") (pinfunction "D12_M10") (pintype "bidirectional"))
      (node (ref "U3") (pin "5") (pinfunction "A4_5") (pintype "bidirectional"))
    )
    (net (code "97") (name "D13") (class "Default")
      (node (ref "CONN1") (pin "PIN63") (pinfunction "D13_PIN63") (pintype "bidirectional"))
      (node (ref "IC1") (pin "N11") (pinfunction "D13_N11") (pintype "bidirectional"))
      (node (ref "U3") (pin "4") (pinfunction "A3_4") (pintype "bidirectional"))
    )
    (net (code "98") (name "D14") (class "Default")
      (node (ref "CONN1") (pin "PIN62") (pinfunction "D14_PIN62") (pintype "bidirectional"))
      (node (ref "IC1") (pin "M09") (pinfunction "D14_M09") (pintype "bidirectional"))
      (node (ref "U3") (pin "3") (pinfunction "A2_3") (pintype "bidirectional"))
    )
    (net (code "99") (name "D15") (class "Default")
      (node (ref "CONN1") (pin "PIN61") (pinfunction "D15_PIN61") (pintype "bidirectional"))
      (node (ref "IC1") (pin "N10") (pinfunction "D15_N10") (pintype "bidirectional"))
      (node (ref "U3") (pin "2") (pinfunction "A1_2") (pintype "bidirectional"))
    )
    (net (code "100") (name "D16") (class "Default")
      (node (ref "CONN1") (pin "PIN58") (pinfunction "D16_PIN58") (pintype "bidirectional"))
      (node (ref "IC1") (pin "N09") (pinfunction "D16_N09") (pintype "bidirectional"))
      (node (ref "IDE") (pin "4") (pinfunction "S_4") (pintype "passive"))
      (node (ref "U2") (pin "9") (pinfunction "A8_9") (pintype "bidirectional"))
    )
    (net (code "101") (name "D17") (class "Default")
      (node (ref "CONN1") (pin "PIN57") (pinfunction "D17_PIN57") (pintype "bidirectional"))
      (node (ref "IC1") (pin "M08") (pinfunction "D17_M08") (pintype "bidirectional"))
      (node (ref "IDE") (pin "6") (pinfunction "S_6") (pintype "passive"))
      (node (ref "U2") (pin "8") (pinfunction "A7_8") (pintype "bidirectional"))
    )
    (net (code "102") (name "D18") (class "Default")
      (node (ref "CONN1") (pin "PIN56") (pinfunction "D18_PIN56") (pintype "bidirectional"))
      (node (ref "IC1") (pin "N08") (pinfunction "D18_N08") (pintype "bidirectional"))
      (node (ref "IDE") (pin "8") (pinfunction "S_8") (pintype "passive"))
      (node (ref "U2") (pin "7") (pinfunction "A6_7") (pintype "bidirectional"))
    )
    (net (code "103") (name "D19") (class "Default")
      (node (ref "CONN1") (pin "PIN55") (pinfunction "D19_PIN55") (pintype "bidirectional"))
      (node (ref "IC1") (pin "N07") (pinfunction "D19_N07") (pintype "bidirectional"))
      (node (ref "IDE") (pin "10") (pinfunction "S_10") (pintype "passive"))
      (node (ref "U2") (pin "6") (pinfunction "A5_6") (pintype "bidirectional"))
    )
    (net (code "104") (name "D20") (class "Default")
      (node (ref "CONN1") (pin "PIN54") (pinfunction "D20_PIN54") (pintype "bidirectional"))
      (node (ref "IC1") (pin "M07") (pinfunction "D20_M07") (pintype "bidirectional"))
      (node (ref "IDE") (pin "12") (pinfunction "S_12") (pintype "passive"))
      (node (ref "U2") (pin "5") (pinfunction "A4_5") (pintype "bidirectional"))
    )
    (net (code "105") (name "D21") (class "Default")
      (node (ref "CONN1") (pin "PIN53") (pinfunction "D21_PIN53") (pintype "bidirectional"))
      (node (ref "IC1") (pin "N06") (pinfunction "D21_N06") (pintype "bidirectional"))
      (node (ref "IDE") (pin "14") (pinfunction "S_14") (pintype "passive"))
      (node (ref "U2") (pin "4") (pinfunction "A3_4") (pintype "bidirectional"))
    )
    (net (code "106") (name "D22") (class "Default")
      (node (ref "CONN1") (pin "PIN52") (pinfunction "D22_PIN52") (pintype "bidirectional"))
      (node (ref "IC1") (pin "M06") (pinfunction "D22_M06") (pintype "bidirectional"))
      (node (ref "IDE") (pin "16") (pinfunction "S_16") (pintype "passive"))
      (node (ref "U2") (pin "3") (pinfunction "A2_3") (pintype "bidirectional"))
    )
    (net (code "107") (name "D23") (class "Default")
      (node (ref "CONN1") (pin "PIN51") (pinfunction "D23_PIN51") (pintype "bidirectional"))
      (node (ref "IC1") (pin "N05") (pinfunction "D23_N05") (pintype "bidirectional"))
      (node (ref "IDE") (pin "18") (pinfunction "S_18") (pintype "passive"))
      (node (ref "U2") (pin "2") (pinfunction "A1_2") (pintype "bidirectional"))
    )
    (net (code "108") (name "D24") (class "Default")
      (node (ref "CONN1") (pin "PIN48") (pinfunction "D24_PIN48") (pintype "bidirectional"))
      (node (ref "IC1") (pin "M05") (pinfunction "D24_M05") (pintype "bidirectional"))
      (node (ref "IDE") (pin "17") (pinfunction "S_17") (pintype "passive"))
      (node (ref "U1") (pin "9") (pinfunction "A8_9") (pintype "bidirectional"))
      (node (ref "XC95144XL") (pin "52") (pinfunction "PB5/2_52") (pintype "input"))
    )
    (net (code "109") (name "D25") (class "Default")
      (node (ref "CONN1") (pin "PIN47") (pinfunction "D25_PIN47") (pintype "bidirectional"))
      (node (ref "IC1") (pin "N04") (pinfunction "D25_N04") (pintype "bidirectional"))
      (node (ref "IDE") (pin "15") (pinfunction "S_15") (pintype "passive"))
      (node (ref "U1") (pin "8") (pinfunction "A7_8") (pintype "bidirectional"))
      (node (ref "XC95144XL") (pin "51") (pinfunction "PB3/17_51") (pintype "input"))
    )
    (net (code "110") (name "D26") (class "Default")
      (node (ref "CONN1") (pin "PIN46") (pinfunction "D26_PIN46") (pintype "bidirectional"))
      (node (ref "IC1") (pin "N03") (pinfunction "D26_N03") (pintype "bidirectional"))
      (node (ref "IDE") (pin "13") (pinfunction "S_13") (pintype "passive"))
      (node (ref "U1") (pin "7") (pinfunction "A6_7") (pintype "bidirectional"))
      (node (ref "XC95144XL") (pin "50") (pinfunction "PB3/15_50") (pintype "input"))
    )
    (net (code "111") (name "D27") (class "Default")
      (node (ref "CONN1") (pin "PIN45") (pinfunction "D27_PIN45") (pintype "bidirectional"))
      (node (ref "IC1") (pin "M04") (pinfunction "D27_M04") (pintype "bidirectional"))
      (node (ref "IDE") (pin "11") (pinfunction "S_11") (pintype "passive"))
      (node (ref "U1") (pin "6") (pinfunction "A5_6") (pintype "bidirectional"))
      (node (ref "XC95144XL") (pin "49") (pinfunction "PB3/14_49") (pintype "input"))
    )
    (net (code "112") (name "D28") (class "Default")
      (node (ref "CONN1") (pin "PIN44") (pinfunction "D28_PIN44") (pintype "bidirectional"))
      (node (ref "IC1") (pin "N02") (pinfunction "D28_N02") (pintype "bidirectional"))
      (node (ref "IDE") (pin "9") (pinfunction "S_9") (pintype "passive"))
      (node (ref "U1") (pin "5") (pinfunction "A4_5") (pintype "bidirectional"))
      (node (ref "XC95144XL") (pin "48") (pinfunction "PB3/10_48") (pintype "input"))
    )
    (net (code "113") (name "D29") (class "Default")
      (node (ref "CONN1") (pin "PIN43") (pinfunction "D29_PIN43") (pintype "bidirectional"))
      (node (ref "IC1") (pin "M03") (pinfunction "D29_M03") (pintype "bidirectional"))
      (node (ref "IDE") (pin "7") (pinfunction "S_7") (pintype "passive"))
      (node (ref "U1") (pin "4") (pinfunction "A3_4") (pintype "bidirectional"))
      (node (ref "XC95144XL") (pin "46") (pinfunction "PB3/7_46") (pintype "input"))
    )
    (net (code "114") (name "D30") (class "Default")
      (node (ref "CONN1") (pin "PIN42") (pinfunction "D30_PIN42") (pintype "bidirectional"))
      (node (ref "IC1") (pin "L04") (pinfunction "D30_L04") (pintype "bidirectional"))
      (node (ref "IDE") (pin "5") (pinfunction "S_5") (pintype "passive"))
      (node (ref "U1") (pin "3") (pinfunction "A2_3") (pintype "bidirectional"))
      (node (ref "XC95144XL") (pin "45") (pinfunction "PB3/12_45") (pintype "input"))
    )
    (net (code "115") (name "D31") (class "Default")
      (node (ref "CONN1") (pin "PIN41") (pinfunction "D31_PIN41") (pintype "bidirectional"))
      (node (ref "IC1") (pin "N01") (pinfunction "D31_N01") (pintype "bidirectional"))
      (node (ref "IDE") (pin "3") (pinfunction "S_3") (pintype "passive"))
      (node (ref "U1") (pin "2") (pinfunction "A1_2") (pintype "bidirectional"))
      (node (ref "XC95144XL") (pin "44") (pinfunction "PB3/4_44") (pintype "input"))
    )
    (net (code "116") (name "DBEN") (class "Default")
      (node (ref "IC1") (pin "M01") (pinfunction "DBEN_M01") (pintype "output"))
    )
    (net (code "117") (name "DQM0") (class "Default")
      (node (ref "IC8") (pin "15") (pinfunction "DQML_15") (pintype "input"))
      (node (ref "XC95144XL") (pin "16") (pinfunction "PB1/2_16") (pintype "input"))
    )
    (net (code "118") (name "DQM1") (class "Default")
      (node (ref "IC8") (pin "39") (pinfunction "DQMH_39") (pintype "input"))
      (node (ref "XC95144XL") (pin "31") (pinfunction "PB1/10_31") (pintype "input"))
    )
    (net (code "119") (name "DQM2") (class "Default")
      (node (ref "IC7") (pin "15") (pinfunction "DQML_15") (pintype "input"))
      (node (ref "XC95144XL") (pin "15") (pinfunction "PB2/17_15") (pintype "input"))
    )
    (net (code "120") (name "DQM3") (class "Default")
      (node (ref "IC7") (pin "39") (pinfunction "DQMH_39") (pintype "input"))
      (node (ref "XC95144XL") (pin "3") (pinfunction "PB2/6_3") (pintype "input"))
    )
    (net (code "121") (name "DRAM0") (class "Default")
      (node (ref "IC8") (pin "2") (pinfunction "DQO_2") (pintype "input"))
      (node (ref "U4") (pin "11") (pinfunction "B8_11") (pintype "bidirectional"))
    )
    (net (code "122") (name "DRAM1") (class "Default")
      (node (ref "IC8") (pin "4") (pinfunction "DQ1_4") (pintype "input"))
      (node (ref "U4") (pin "12") (pinfunction "B7_12") (pintype "bidirectional"))
    )
    (net (code "123") (name "DRAM2") (class "Default")
      (node (ref "IC8") (pin "5") (pinfunction "DQ2_5") (pintype "input"))
      (node (ref "U4") (pin "13") (pinfunction "B6_13") (pintype "bidirectional"))
    )
    (net (code "124") (name "DRAM3") (class "Default")
      (node (ref "IC8") (pin "7") (pinfunction "DQ3_7") (pintype "input"))
      (node (ref "U4") (pin "14") (pinfunction "B5_14") (pintype "bidirectional"))
    )
    (net (code "125") (name "DRAM4") (class "Default")
      (node (ref "IC8") (pin "8") (pinfunction "DQ4_8") (pintype "input"))
      (node (ref "U4") (pin "15") (pinfunction "B4_15") (pintype "bidirectional"))
    )
    (net (code "126") (name "DRAM5") (class "Default")
      (node (ref "IC8") (pin "10") (pinfunction "DQ5_10") (pintype "input"))
      (node (ref "U4") (pin "16") (pinfunction "B3_16") (pintype "bidirectional"))
    )
    (net (code "127") (name "DRAM6") (class "Default")
      (node (ref "IC8") (pin "11") (pinfunction "DQ6_11") (pintype "input"))
      (node (ref "U4") (pin "17") (pinfunction "B2_17") (pintype "bidirectional"))
    )
    (net (code "128") (name "DRAM7") (class "Default")
      (node (ref "IC8") (pin "13") (pinfunction "DQ7_13") (pintype "input"))
      (node (ref "U4") (pin "18") (pinfunction "B1_18") (pintype "bidirectional"))
    )
    (net (code "129") (name "DRAM8") (class "Default")
      (node (ref "IC8") (pin "42") (pinfunction "DQ8_42") (pintype "input"))
      (node (ref "U3") (pin "11") (pinfunction "B8_11") (pintype "bidirectional"))
    )
    (net (code "130") (name "DRAM9") (class "Default")
      (node (ref "IC8") (pin "44") (pinfunction "DQ9_44") (pintype "input"))
      (node (ref "U3") (pin "12") (pinfunction "B7_12") (pintype "bidirectional"))
    )
    (net (code "131") (name "DRAM10") (class "Default")
      (node (ref "IC8") (pin "45") (pinfunction "DQ10_45") (pintype "input"))
      (node (ref "U3") (pin "13") (pinfunction "B6_13") (pintype "bidirectional"))
    )
    (net (code "132") (name "DRAM11") (class "Default")
      (node (ref "IC8") (pin "47") (pinfunction "DQ11_47") (pintype "input"))
      (node (ref "U3") (pin "14") (pinfunction "B5_14") (pintype "bidirectional"))
    )
    (net (code "133") (name "DRAM12") (class "Default")
      (node (ref "IC8") (pin "48") (pinfunction "DQ12_48") (pintype "input"))
      (node (ref "U3") (pin "15") (pinfunction "B4_15") (pintype "bidirectional"))
    )
    (net (code "134") (name "DRAM13") (class "Default")
      (node (ref "IC8") (pin "50") (pinfunction "DQ13_50") (pintype "input"))
      (node (ref "U3") (pin "16") (pinfunction "B3_16") (pintype "bidirectional"))
    )
    (net (code "135") (name "DRAM14") (class "Default")
      (node (ref "IC8") (pin "51") (pinfunction "DQM_51") (pintype "input"))
      (node (ref "U3") (pin "17") (pinfunction "B2_17") (pintype "bidirectional"))
    )
    (net (code "136") (name "DRAM15") (class "Default")
      (node (ref "IC8") (pin "53") (pinfunction "DQ15_53") (pintype "input"))
      (node (ref "U3") (pin "18") (pinfunction "B1_18") (pintype "bidirectional"))
    )
    (net (code "137") (name "DRAM16") (class "Default")
      (node (ref "IC7") (pin "2") (pinfunction "DQO_2") (pintype "input"))
      (node (ref "U2") (pin "11") (pinfunction "B8_11") (pintype "bidirectional"))
    )
    (net (code "138") (name "DRAM17") (class "Default")
      (node (ref "IC7") (pin "4") (pinfunction "DQ1_4") (pintype "input"))
      (node (ref "U2") (pin "12") (pinfunction "B7_12") (pintype "bidirectional"))
    )
    (net (code "139") (name "DRAM18") (class "Default")
      (node (ref "IC7") (pin "5") (pinfunction "DQ2_5") (pintype "input"))
      (node (ref "U2") (pin "13") (pinfunction "B6_13") (pintype "bidirectional"))
    )
    (net (code "140") (name "DRAM19") (class "Default")
      (node (ref "IC7") (pin "7") (pinfunction "DQ3_7") (pintype "input"))
      (node (ref "U2") (pin "14") (pinfunction "B5_14") (pintype "bidirectional"))
    )
    (net (code "141") (name "DRAM20") (class "Default")
      (node (ref "IC7") (pin "8") (pinfunction "DQ4_8") (pintype "input"))
      (node (ref "U2") (pin "15") (pinfunction "B4_15") (pintype "bidirectional"))
    )
    (net (code "142") (name "DRAM21") (class "Default")
      (node (ref "IC7") (pin "10") (pinfunction "DQ5_10") (pintype "input"))
      (node (ref "U2") (pin "16") (pinfunction "B3_16") (pintype "bidirectional"))
    )
    (net (code "143") (name "DRAM22") (class "Default")
      (node (ref "IC7") (pin "11") (pinfunction "DQ6_11") (pintype "input"))
      (node (ref "U2") (pin "17") (pinfunction "B2_17") (pintype "bidirectional"))
    )
    (net (code "144") (name "DRAM23") (class "Default")
      (node (ref "IC7") (pin "13") (pinfunction "DQ7_13") (pintype "input"))
      (node (ref "U2") (pin "18") (pinfunction "B1_18") (pintype "bidirectional"))
    )
    (net (code "145") (name "DRAM24") (class "Default")
      (node (ref "IC7") (pin "42") (pinfunction "DQ8_42") (pintype "input"))
      (node (ref "U1") (pin "11") (pinfunction "B8_11") (pintype "bidirectional"))
    )
    (net (code "146") (name "DRAM25") (class "Default")
      (node (ref "IC7") (pin "44") (pinfunction "DQ9_44") (pintype "input"))
      (node (ref "U1") (pin "12") (pinfunction "B7_12") (pintype "bidirectional"))
    )
    (net (code "147") (name "DRAM26") (class "Default")
      (node (ref "IC7") (pin "45") (pinfunction "DQ10_45") (pintype "input"))
      (node (ref "U1") (pin "13") (pinfunction "B6_13") (pintype "bidirectional"))
    )
    (net (code "148") (name "DRAM27") (class "Default")
      (node (ref "IC7") (pin "47") (pinfunction "DQ11_47") (pintype "input"))
      (node (ref "U1") (pin "14") (pinfunction "B5_14") (pintype "bidirectional"))
    )
    (net (code "149") (name "DRAM28") (class "Default")
      (node (ref "IC7") (pin "48") (pinfunction "DQ12_48") (pintype "input"))
      (node (ref "U1") (pin "15") (pinfunction "B4_15") (pintype "bidirectional"))
    )
    (net (code "150") (name "DRAM29") (class "Default")
      (node (ref "IC7") (pin "50") (pinfunction "DQ13_50") (pintype "input"))
      (node (ref "U1") (pin "16") (pinfunction "B3_16") (pintype "bidirectional"))
    )
    (net (code "151") (name "DRAM30") (class "Default")
      (node (ref "IC7") (pin "51") (pinfunction "DQM_51") (pintype "input"))
      (node (ref "U1") (pin "17") (pinfunction "B2_17") (pintype "bidirectional"))
    )
    (net (code "152") (name "DRAM31") (class "Default")
      (node (ref "IC7") (pin "53") (pinfunction "DQ15_53") (pintype "input"))
      (node (ref "U1") (pin "18") (pinfunction "B1_18") (pintype "bidirectional"))
    )
    (net (code "153") (name "DS20") (class "Default")
      (node (ref "CONN1") (pin "PIN92") (pinfunction "~{DS}_PIN92") (pintype "bidirectional"))
      (node (ref "XC95144XL") (pin "133") (pinfunction "PB4/3_133") (pintype "input"))
    )
    (net (code "154") (name "DS30") (class "Default")
      (node (ref "IC1") (pin "K02") (pinfunction "DS_K02") (pintype "output"))
      (node (ref "RN3") (pin "2") (pinfunction "2_2") (pintype "passive"))
      (node (ref "XC95144XL") (pin "68") (pinfunction "PB5/10_68") (pintype "input"))
    )
    (net (code "155") (name "DS30ACK0") (class "Default")
      (node (ref "IC1") (pin "F01") (pinfunction "DSACK0_F01") (pintype "input"))
      (node (ref "XC95144XL") (pin "79") (pinfunction "PB7/10_79") (pintype "input"))
    )
    (net (code "156") (name "DS30ACK1") (class "Default")
      (node (ref "IC1") (pin "G02") (pinfunction "DSACK1_G02") (pintype "input"))
      (node (ref "XC95144XL") (pin "78") (pinfunction "PB7/8_78") (pintype "input"))
    )
    (net (code "157") (name "DSACK0") (class "Default")
      (node (ref "CONN1") (pin "PIN98") (pinfunction "~{DSACK0}_PIN98") (pintype "bidirectional"))
      (node (ref "XC95144XL") (pin "135") (pinfunction "PB4/10_135") (pintype "input"))
    )
    (net (code "158") (name "DSACK1") (class "Default")
      (node (ref "CONN1") (pin "PIN97") (pinfunction "~{DSACK1}_PIN97") (pintype "bidirectional"))
      (node (ref "XC95144XL") (pin "136") (pinfunction "PB4/14_136") (pintype "input"))
    )
    (net (code "159") (name "EXP_BG") (class "Default")
      (node (ref "CONN1") (pin "PIN112") (pinfunction "~{EXP_BG}_PIN112") (pintype "bidirectional"))
      (node (ref "XC95144XL") (pin "139") (pinfunction "PB4/16_139") (pintype "input"))
    )
    (net (code "160") (name "EXP_BR") (class "Default")
      (node (ref "CONN1") (pin "PIN114") (pinfunction "~{EXP_BR}_PIN114") (pintype "bidirectional"))
      (node (ref "XC95144XL") (pin "140") (pinfunction "PB4/17_140") (pintype "input"))
    )
    (net (code "161") (name "FC0") (class "Default")
      (node (ref "CONN1") (pin "PIN105") (pinfunction "FC0_PIN105") (pintype "bidirectional"))
      (node (ref "IC1") (pin "D02") (pinfunction "FC0_D02") (pintype "output"))
      (node (ref "XC95144XL") (pin "85") (pinfunction "PB7/12_85") (pintype "input"))
    )
    (net (code "162") (name "FC1") (class "Default")
      (node (ref "CONN1") (pin "PIN104") (pinfunction "FC1_PIN104") (pintype "bidirectional"))
      (node (ref "IC1") (pin "C01") (pinfunction "FC1_C01") (pintype "output"))
      (node (ref "XC95144XL") (pin "82") (pinfunction "PB7/11_82") (pintype "input"))
    )
    (net (code "163") (name "FC2") (class "Default")
      (node (ref "CONN1") (pin "PIN103") (pinfunction "FC2_PIN103") (pintype "bidirectional"))
      (node (ref "IC1") (pin "D01") (pinfunction "FC2_D01") (pintype "output"))
      (node (ref "XC95144XL") (pin "81") (pinfunction "PB7/13_81") (pintype "input"))
    )
    (net (code "164") (name "FIRE0") (class "Default")
      (node (ref "CONN1") (pin "PIN124") (pinfunction "~{FIRE1}_PIN124") (pintype "bidirectional"))
    )
    (net (code "165") (name "FIRE1") (class "Default")
      (node (ref "CONN1") (pin "PIN123") (pinfunction "~{FIRE0}_PIN123") (pintype "bidirectional"))
    )
    (net (code "166") (name "GND") (class "Default")
      (node (ref "5VPWR") (pin "1") (pinfunction "1_1") (pintype "passive"))
      (node (ref "C1") (pin "2") (pinfunction "P$2_2") (pintype "passive"))
      (node (ref "C10") (pin "2") (pinfunction "2_2") (pintype "passive"))
      (node (ref "C11") (pin "2") (pinfunction "2_2") (pintype "passive"))
      (node (ref "C12") (pin "2") (pinfunction "2_2") (pintype "passive"))
      (node (ref "C13") (pin "2") (pinfunction "2_2") (pintype "passive"))
      (node (ref "C14") (pin "2") (pinfunction "2_2") (pintype "passive"))
      (node (ref "C15") (pin "2") (pinfunction "2_2") (pintype "passive"))
      (node (ref "C16") (pin "2") (pinfunction "P$2_2") (pintype "passive"))
      (node (ref "C17") (pin "2") (pinfunction "P$2_2") (pintype "passive"))
      (node (ref "C18") (pin "2") (pinfunction "P$2_2") (pintype "passive"))
      (node (ref "C19") (pin "2") (pinfunction "2_2") (pintype "passive"))
      (node (ref "C2") (pin "2") (pinfunction "P$2_2") (pintype "passive"))
      (node (ref "C24") (pin "2") (pinfunction "P$2_2") (pintype "passive"))
      (node (ref "C27") (pin "2") (pinfunction "2_2") (pintype "passive"))
      (node (ref "C28") (pin "2") (pinfunction "2_2") (pintype "passive"))
      (node (ref "C29") (pin "2") (pinfunction "P$2_2") (pintype "passive"))
      (node (ref "C3") (pin "2") (pinfunction "P$2_2") (pintype "passive"))
      (node (ref "C4") (pin "2") (pinfunction "2_2") (pintype "passive"))
      (node (ref "C5") (pin "2") (pinfunction "2_2") (pintype "passive"))
      (node (ref "C6") (pin "2") (pinfunction "P$2_2") (pintype "passive"))
      (node (ref "C7") (pin "2") (pinfunction "2_2") (pintype "passive"))
      (node (ref "C8") (pin "2") (pinfunction "P$2_2") (pintype "passive"))
      (node (ref "C9") (pin "2") (pinfunction "P$2_2") (pintype "passive"))
      (node (ref "CDIS") (pin "1") (pinfunction "1_1") (pintype "passive"))
      (node (ref "CONN1") (pin "PIN101") (pinfunction "DGND_PIN101") (pintype "power_in"))
      (node (ref "CONN1") (pin "PIN135") (pinfunction "DGND_PIN135") (pintype "power_in"))
      (node (ref "CONN1") (pin "PIN137") (pinfunction "DGND_PIN137") (pintype "power_in"))
      (node (ref "CONN1") (pin "PIN145") (pinfunction "DGND_PIN145") (pintype "power_in"))
      (node (ref "CONN1") (pin "PIN155") (pinfunction "DGND_PIN155") (pintype "power_in"))
      (node (ref "CONN1") (pin "PIN175") (pinfunction "DGND_PIN175") (pintype "power_in"))
      (node (ref "CONN1") (pin "PIN19") (pinfunction "DGND_PIN19") (pintype "power_in"))
      (node (ref "CONN1") (pin "PIN29") (pinfunction "DGND_PIN29") (pintype "power_in"))
      (node (ref "CONN1") (pin "PIN39") (pinfunction "DGND_PIN39") (pintype "power_in"))
      (node (ref "CONN1") (pin "PIN49") (pinfunction "DGND_PIN49") (pintype "power_in"))
      (node (ref "CONN1") (pin "PIN59") (pinfunction "DGND_PIN59") (pintype "power_in"))
      (node (ref "CONN1") (pin "PIN69") (pinfunction "DGND_PIN69") (pintype "power_in"))
      (node (ref "CONN1") (pin "PIN79") (pinfunction "DGND_PIN79") (pintype "power_in"))
      (node (ref "CONN1") (pin "PIN9") (pinfunction "DGND_PIN9") (pintype "power_in"))
      (node (ref "ESPHEADER") (pin "7") (pinfunction "7_7") (pintype "passive"))
      (node (ref "IC2") (pin "1") (pinfunction "ADJ_1") (pintype "input"))
      (node (ref "IC7") (pin "12") (pinfunction "VSSQ(2)_12") (pintype "input"))
      (node (ref "IC7") (pin "28") (pinfunction "VSS(1)_28") (pintype "input"))
      (node (ref "IC7") (pin "41") (pinfunction "VSS(2)_41") (pintype "input"))
      (node (ref "IC7") (pin "46") (pinfunction "VSSQ(3)_46") (pintype "input"))
      (node (ref "IC7") (pin "52") (pinfunction "VSSQ(4)_52") (pintype "input"))
      (node (ref "IC7") (pin "54") (pinfunction "VSS(3)_54") (pintype "input"))
      (node (ref "IC7") (pin "6") (pinfunction "VSSQ(1)_6") (pintype "input"))
      (node (ref "IC8") (pin "12") (pinfunction "VSSQ(2)_12") (pintype "input"))
      (node (ref "IC8") (pin "28") (pinfunction "VSS(1)_28") (pintype "input"))
      (node (ref "IC8") (pin "41") (pinfunction "VSS(2)_41") (pintype "input"))
      (node (ref "IC8") (pin "46") (pinfunction "VSSQ(3)_46") (pintype "input"))
      (node (ref "IC8") (pin "52") (pinfunction "VSSQ(4)_52") (pintype "input"))
      (node (ref "IC8") (pin "54") (pinfunction "VSS(3)_54") (pintype "input"))
      (node (ref "IC8") (pin "6") (pinfunction "VSSQ(1)_6") (pintype "input"))
      (node (ref "IDE") (pin "19") (pinfunction "S_19") (pintype "passive"))
      (node (ref "IDE") (pin "2") (pinfunction "S_2") (pintype "passive"))
      (node (ref "IDE") (pin "22") (pinfunction "S_22") (pintype "passive"))
      (node (ref "IDE") (pin "24") (pinfunction "S_24") (pintype "passive"))
      (node (ref "IDE") (pin "26") (pinfunction "S_26") (pintype "passive"))
      (node (ref "IDE") (pin "30") (pinfunction "S_30") (pintype "passive"))
      (node (ref "IDE") (pin "40") (pinfunction "S_40") (pintype "passive"))
      (node (ref "IDE") (pin "43") (pinfunction "S_43") (pintype "passive"))
      (node (ref "IDE") (pin "44") (pinfunction "S_44") (pintype "passive"))
      (node (ref "JTAG1") (pin "5") (pinfunction "5_5") (pintype "passive"))
      (node (ref "MMUDIS") (pin "1") (pinfunction "1_1") (pintype "passive"))
      (node (ref "OSC2") (pin "2") (pinfunction "GND_2") (pintype "power_in"))
      (node (ref "R5") (pin "2") (pinfunction "2_2") (pintype "passive"))
      (node (ref "U1") (pin "10") (pinfunction "GND_10") (pintype "passive"))
      (node (ref "U2") (pin "10") (pinfunction "GND_10") (pintype "passive"))
      (node (ref "U3") (pin "10") (pinfunction "GND_10") (pintype "passive"))
      (node (ref "U4") (pin "10") (pinfunction "GND_10") (pintype "passive"))
      (node (ref "XC95144XL") (pin "108") (pinfunction "GND(10)_108") (pintype "input"))
      (node (ref "XC95144XL") (pin "114") (pinfunction "GND(11)_114") (pintype "input"))
      (node (ref "XC95144XL") (pin "123") (pinfunction "GND(12)_123") (pintype "input"))
      (node (ref "XC95144XL") (pin "144") (pinfunction "GND(13)_144") (pintype "input"))
      (node (ref "XC95144XL") (pin "18") (pinfunction "GND(1)_18") (pintype "input"))
      (node (ref "XC95144XL") (pin "29") (pinfunction "GND(2)_29") (pintype "input"))
      (node (ref "XC95144XL") (pin "36") (pinfunction "GND(3)_36") (pintype "input"))
      (node (ref "XC95144XL") (pin "47") (pinfunction "GND(4)_47") (pintype "input"))
      (node (ref "XC95144XL") (pin "62") (pinfunction "GND(5)_62") (pintype "input"))
      (node (ref "XC95144XL") (pin "72") (pinfunction "GND(6)_72") (pintype "input"))
      (node (ref "XC95144XL") (pin "89") (pinfunction "GND(7)_89") (pintype "input"))
      (node (ref "XC95144XL") (pin "90") (pinfunction "GND(8)_90") (pintype "input"))
      (node (ref "XC95144XL") (pin "99") (pinfunction "GND(9)_99") (pintype "input"))
    )
    (net (code "167") (name "HALT") (class "Default")
      (node (ref "IC1") (pin "H02") (pinfunction "HALT_H02") (pintype "input"))
      (node (ref "XC95144XL") (pin "76") (pinfunction "PB7/6_76") (pintype "input"))
    )
    (net (code "168") (name "IDECS0") (class "Default")
      (node (ref "IDE") (pin "37") (pinfunction "S_37") (pintype "passive"))
      (node (ref "XC95144XL") (pin "58") (pinfunction "PB5/11_58") (pintype "input"))
    )
    (net (code "169") (name "IDECS1") (class "Default")
      (node (ref "IDE") (pin "38") (pinfunction "S_38") (pintype "passive"))
      (node (ref "XC95144XL") (pin "59") (pinfunction "PB5/3_59") (pintype "input"))
    )
    (net (code "170") (name "IDEINT") (class "Default")
      (node (ref "IDE") (pin "31") (pinfunction "S_31") (pintype "passive"))
      (node (ref "R5") (pin "1") (pinfunction "1_1") (pintype "passive"))
      (node (ref "XC95144XL") (pin "57") (pinfunction "PB5/9_57") (pintype "input"))
    )
    (net (code "171") (name "IDELED") (class "Default")
      (node (ref "IDE") (pin "39") (pinfunction "S_39") (pintype "passive"))
      (node (ref "XC95144XL") (pin "71") (pinfunction "PB7/2_71") (pintype "input"))
    )
    (net (code "172") (name "IDEWAIT") (class "Default")
      (node (ref "IDE") (pin "27") (pinfunction "S_27") (pintype "passive"))
      (node (ref "R4") (pin "1") (pinfunction "1_1") (pintype "passive"))
      (node (ref "XC95144XL") (pin "56") (pinfunction "PB5/8_56") (pintype "input"))
    )
    (net (code "173") (name "INT2") (class "Default")
      (node (ref "CONN1") (pin "PIN119") (pinfunction "~{INT2}_PIN119") (pintype "bidirectional"))
      (node (ref "XC95144XL") (pin "143") (pinfunction "PB2/2_143") (pintype "input"))
    )
    (net (code "174") (name "INT6") (class "Default")
      (node (ref "CONN1") (pin "PIN120") (pinfunction "~{INT6}_PIN120") (pintype "bidirectional"))
    )
    (net (code "175") (name "IOR") (class "Default")
      (node (ref "IDE") (pin "25") (pinfunction "S_25") (pintype "passive"))
      (node (ref "XC95144XL") (pin "54") (pinfunction "PB5/6_54") (pintype "input"))
    )
    (net (code "176") (name "IOW") (class "Default")
      (node (ref "IDE") (pin "23") (pinfunction "S_23") (pintype "passive"))
      (node (ref "XC95144XL") (pin "53") (pinfunction "PB5/5_53") (pintype "input"))
    )
    (net (code "177") (name "IPL0") (class "Default")
      (node (ref "CONN1") (pin "PIN83") (pinfunction "~{IPL0}_PIN83") (pintype "bidirectional"))
      (node (ref "IC1") (pin "H13") (pinfunction "IPL0_H13") (pintype "input"))
    )
    (net (code "178") (name "IPL1") (class "Default")
      (node (ref "CONN1") (pin "PIN82") (pinfunction "~{IPL1}_PIN82") (pintype "bidirectional"))
      (node (ref "IC1") (pin "G13") (pinfunction "IPL1_G13") (pintype "input"))
    )
    (net (code "179") (name "IPL2") (class "Default")
      (node (ref "CONN1") (pin "PIN81") (pinfunction "~{IPL2}_PIN81") (pintype "bidirectional"))
      (node (ref "IC1") (pin "G12") (pinfunction "IPL2_G12") (pintype "input"))
    )
    (net (code "180") (name "MMUDIS") (class "Default")
      (node (ref "IC1") (pin "F13") (pinfunction "MMUDIS_F13") (pintype "input"))
      (node (ref "MMUDIS") (pin "2") (pinfunction "2_2") (pintype "passive"))
      (node (ref "RN2") (pin "1") (pinfunction "1_1") (pintype "passive"))
    )
    (net (code "181") (name "PUNT") (class "Default")
      (node (ref "CONN1") (pin "PIN117") (pinfunction "~{PUNT}_PIN117") (pintype "bidirectional"))
      (node (ref "XC95144XL") (pin "142") (pinfunction "PB2/1_142") (pintype "input"))
    )
    (net (code "182") (name "RAMCS") (class "Default")
      (node (ref "IC7") (pin "19") (pinfunction "CS#_19") (pintype "input"))
      (node (ref "IC8") (pin "19") (pinfunction "CS#_19") (pintype "input"))
      (node (ref "XC95144XL") (pin "21") (pinfunction "PB1/8_21") (pintype "input"))
    )
    (net (code "183") (name "RAMOE") (class "Default")
      (node (ref "U1") (pin "19") (pinfunction "~{OE}_19") (pintype "input"))
      (node (ref "U2") (pin "19") (pinfunction "~{OE}_19") (pintype "input"))
      (node (ref "U3") (pin "19") (pinfunction "~{OE}_19") (pintype "input"))
      (node (ref "U4") (pin "19") (pinfunction "~{OE}_19") (pintype "input"))
      (node (ref "XC95144XL") (pin "2") (pinfunction "PB2/5_2") (pintype "input"))
    )
    (net (code "184") (name "RAMWE") (class "Default")
      (node (ref "IC7") (pin "16") (pinfunction "WE#_16") (pintype "input"))
      (node (ref "IC8") (pin "16") (pinfunction "WE#_16") (pintype "input"))
      (node (ref "XC95144XL") (pin "17") (pinfunction "PB1/3_17") (pintype "input"))
    )
    (net (code "185") (name "RAS") (class "Default")
      (node (ref "IC7") (pin "18") (pinfunction "RAS#_18") (pintype "input"))
      (node (ref "IC8") (pin "18") (pinfunction "RAS#_18") (pintype "input"))
      (node (ref "XC95144XL") (pin "20") (pinfunction "PB1/6_20") (pintype "input"))
    )
    (net (code "186") (name "REFILL") (class "Default")
      (node (ref "IC1") (pin "J13") (pinfunction "REFILL_J13") (pintype "output"))
    )
    (net (code "187") (name "RESET") (class "Default")
      (node (ref "CONN1") (pin "PIN118") (pinfunction "~{RESET}_PIN118") (pintype "bidirectional"))
      (node (ref "IDE") (pin "1") (pinfunction "S_1") (pintype "passive"))
      (node (ref "XC95144XL") (pin "40") (pinfunction "PB3/9_40") (pintype "input"))
    )
    (net (code "188") (name "RSTO") (class "Default")
      (node (ref "CONN1") (pin "PIN85") (pinfunction "RTS_PIN85") (pintype "bidirectional"))
      (node (ref "IC1") (pin "F12") (pinfunction "RESET_F12") (pintype "bidirectional"))
    )
    (net (code "189") (name "RW20") (class "Default")
      (node (ref "CONN1") (pin "PIN93") (pinfunction "R/~{W}_PIN93") (pintype "bidirectional"))
      (node (ref "XC95144XL") (pin "134") (pinfunction "PB4/12_134") (pintype "input"))
    )
    (net (code "190") (name "RW30") (class "Default")
      (node (ref "IC1") (pin "L03") (pinfunction "R/~{W}_L03") (pintype "output"))
      (node (ref "RN3") (pin "1") (pinfunction "1_1") (pintype "passive"))
      (node (ref "XC95144XL") (pin "64") (pinfunction "PB5/15_64") (pintype "input"))
    )
    (net (code "191") (name "RXD") (class "Default")
      (node (ref "CONN1") (pin "PIN127") (pinfunction "~{RXD}_PIN127") (pintype "bidirectional"))
      (node (ref "XC95144XL") (pin "34") (pinfunction "PB3/6_34") (pintype "input"))
    )
    (net (code "192") (name "RXD_EXT") (class "Default")
      (node (ref "ESPHEADER") (pin "1") (pinfunction "1_1") (pintype "passive"))
      (node (ref "XC95144XL") (pin "43") (pinfunction "PB3/11_43") (pintype "input"))
    )
    (net (code "193") (name "SIZ0") (class "Default")
      (node (ref "CONN1") (pin "PIN90") (pinfunction "SIZE0_PIN90") (pintype "bidirectional"))
      (node (ref "IC1") (pin "L02") (pinfunction "SIZ0_L02") (pintype "output"))
      (node (ref "XC95144XL") (pin "61") (pinfunction "PB5/14_61") (pintype "input"))
    )
    (net (code "194") (name "SIZ1") (class "Default")
      (node (ref "CONN1") (pin "PIN89") (pinfunction "SIZE1_PIN89") (pintype "bidirectional"))
      (node (ref "IC1") (pin "K03") (pinfunction "SIZ1_K03") (pintype "output"))
      (node (ref "XC95144XL") (pin "69") (pinfunction "PB5/17_69") (pintype "input"))
    )
    (net (code "195") (name "STATUS") (class "Default")
      (node (ref "IC1") (pin "J12") (pinfunction "STATUS_J12") (pintype "output"))
    )
    (net (code "196") (name "STERM") (class "Default")
      (node (ref "IC1") (pin "G01") (pinfunction "STERM_G01") (pintype "input"))
      (node (ref "XC95144XL") (pin "77") (pinfunction "PB7/7_77") (pintype "input"))
    )
    (net (code "197") (name "TCK") (class "Default")
      (node (ref "JTAG1") (pin "4") (pinfunction "4_4") (pintype "passive"))
      (node (ref "XC95144XL") (pin "67") (pinfunction "TCK_67") (pintype "input"))
    )
    (net (code "198") (name "TDI") (class "Default")
      (node (ref "JTAG1") (pin "2") (pinfunction "2_2") (pintype "passive"))
      (node (ref "XC95144XL") (pin "63") (pinfunction "TDI_63") (pintype "input"))
    )
    (net (code "199") (name "TDO") (class "Default")
      (node (ref "JTAG1") (pin "3") (pinfunction "3_3") (pintype "passive"))
      (node (ref "XC95144XL") (pin "122") (pinfunction "TDO_122") (pintype "input"))
    )
    (net (code "200") (name "TMS") (class "Default")
      (node (ref "JTAG1") (pin "1") (pinfunction "1_1") (pintype "passive"))
      (node (ref "XC95144XL") (pin "65") (pinfunction "TMS_65") (pintype "input"))
    )
    (net (code "201") (name "TXD") (class "Default")
      (node (ref "CONN1") (pin "PIN128") (pinfunction "~{TXD}_PIN128") (pintype "bidirectional"))
      (node (ref "XC95144XL") (pin "33") (pinfunction "PB3/5_33") (pintype "input"))
    )
    (net (code "202") (name "TXD_EXT") (class "Default")
      (node (ref "ESPHEADER") (pin "8") (pinfunction "8_8") (pintype "passive"))
      (node (ref "XC95144XL") (pin "41") (pinfunction "PB3/3_41") (pintype "input"))
    )
    (net (code "203") (name "VCC") (class "Default")
      (node (ref "5VPWR") (pin "2") (pinfunction "2_2") (pintype "passive"))
      (node (ref "C16") (pin "1") (pinfunction "P$1_1") (pintype "passive"))
      (node (ref "C17") (pin "1") (pinfunction "P$1_1") (pintype "passive"))
      (node (ref "C18") (pin "1") (pinfunction "P$1_1") (pintype "passive"))
      (node (ref "C2") (pin "1") (pinfunction "P$1_1") (pintype "passive"))
      (node (ref "C24") (pin "1") (pinfunction "P$1_1") (pintype "passive"))
      (node (ref "C27") (pin "1") (pinfunction "1_1") (pintype "passive"))
      (node (ref "C28") (pin "1") (pinfunction "1_1") (pintype "passive"))
      (node (ref "C29") (pin "1") (pinfunction "P$1_1") (pintype "passive"))
      (node (ref "CONN1") (pin "PIN10") (pinfunction "VCC_PIN10") (pintype "power_in"))
      (node (ref "CONN1") (pin "PIN102") (pinfunction "VCC_PIN102") (pintype "power_in"))
      (node (ref "CONN1") (pin "PIN146") (pinfunction "VCC_PIN146") (pintype "power_in"))
      (node (ref "CONN1") (pin "PIN156") (pinfunction "VCC_PIN156") (pintype "power_in"))
      (node (ref "CONN1") (pin "PIN176") (pinfunction "VCC_PIN176") (pintype "power_in"))
      (node (ref "CONN1") (pin "PIN20") (pinfunction "VCC_PIN20") (pintype "power_in"))
      (node (ref "CONN1") (pin "PIN50") (pinfunction "VCC_PIN50") (pintype "power_in"))
      (node (ref "CONN1") (pin "PIN60") (pinfunction "VCC_PIN60") (pintype "power_in"))
      (node (ref "CONN1") (pin "PIN70") (pinfunction "VCC_PIN70") (pintype "power_in"))
      (node (ref "CONN1") (pin "PIN80") (pinfunction "VCC_PIN80") (pintype "power_in"))
      (node (ref "IC2") (pin "3") (pinfunction "IN_3") (pintype "input"))
      (node (ref "IDE") (pin "41") (pinfunction "S_41") (pintype "passive"))
      (node (ref "IDE") (pin "42") (pinfunction "S_42") (pintype "passive"))
      (node (ref "R4") (pin "2") (pinfunction "2_2") (pintype "passive"))
      (node (ref "RN2") (pin "5") (pinfunction "5_5") (pintype "passive"))
      (node (ref "RN2") (pin "6") (pinfunction "6_6") (pintype "passive"))
      (node (ref "RN2") (pin "7") (pinfunction "7_7") (pintype "passive"))
      (node (ref "RN2") (pin "8") (pinfunction "8_8") (pintype "passive"))
      (node (ref "RN3") (pin "5") (pinfunction "5_5") (pintype "passive"))
      (node (ref "RN3") (pin "6") (pinfunction "6_6") (pintype "passive"))
      (node (ref "RN3") (pin "7") (pinfunction "7_7") (pintype "passive"))
      (node (ref "RN3") (pin "8") (pinfunction "8_8") (pintype "passive"))
    )
    (net (code "204") (name "VCC33") (class "Default")
      (node (ref "C1") (pin "1") (pinfunction "P$1_1") (pintype "passive"))
      (node (ref "C10") (pin "1") (pinfunction "1_1") (pintype "passive"))
      (node (ref "C11") (pin "1") (pinfunction "1_1") (pintype "passive"))
      (node (ref "C12") (pin "1") (pinfunction "1_1") (pintype "passive"))
      (node (ref "C13") (pin "1") (pinfunction "1_1") (pintype "passive"))
      (node (ref "C14") (pin "1") (pinfunction "1_1") (pintype "passive"))
      (node (ref "C15") (pin "1") (pinfunction "1_1") (pintype "passive"))
      (node (ref "C19") (pin "1") (pinfunction "1_1") (pintype "passive"))
      (node (ref "C3") (pin "1") (pinfunction "P$1_1") (pintype "passive"))
      (node (ref "C4") (pin "1") (pinfunction "1_1") (pintype "passive"))
      (node (ref "C5") (pin "1") (pinfunction "1_1") (pintype "passive"))
      (node (ref "C6") (pin "1") (pinfunction "P$1_1") (pintype "passive"))
      (node (ref "C7") (pin "1") (pinfunction "1_1") (pintype "passive"))
      (node (ref "C8") (pin "1") (pinfunction "P$1_1") (pintype "passive"))
      (node (ref "C9") (pin "1") (pinfunction "P$1_1") (pintype "passive"))
      (node (ref "ESPHEADER") (pin "2") (pinfunction "2_2") (pintype "passive"))
      (node (ref "ESPHEADER") (pin "6") (pinfunction "6_6") (pintype "passive"))
      (node (ref "IC2") (pin "2") (pinfunction "OUT_2") (pintype "output"))
      (node (ref "IC2") (pin "4") (pinfunction "OUT_4") (pintype "output"))
      (node (ref "IC7") (pin "1") (pinfunction "VDD(1)_1") (pintype "input"))
      (node (ref "IC7") (pin "14") (pinfunction "VDD(2)_14") (pintype "input"))
      (node (ref "IC7") (pin "27") (pinfunction "VDD(3)_27") (pintype "input"))
      (node (ref "IC7") (pin "3") (pinfunction "VDDQ(1)_3") (pintype "input"))
      (node (ref "IC7") (pin "43") (pinfunction "VDDQ(3)_43") (pintype "input"))
      (node (ref "IC7") (pin "49") (pinfunction "VDDQ(4)_49") (pintype "input"))
      (node (ref "IC7") (pin "9") (pinfunction "VDDQ(2)_9") (pintype "input"))
      (node (ref "IC8") (pin "1") (pinfunction "VDD(1)_1") (pintype "input"))
      (node (ref "IC8") (pin "14") (pinfunction "VDD(2)_14") (pintype "input"))
      (node (ref "IC8") (pin "27") (pinfunction "VDD(3)_27") (pintype "input"))
      (node (ref "IC8") (pin "3") (pinfunction "VDDQ(1)_3") (pintype "input"))
      (node (ref "IC8") (pin "43") (pinfunction "VDDQ(3)_43") (pintype "input"))
      (node (ref "IC8") (pin "49") (pinfunction "VDDQ(4)_49") (pintype "input"))
      (node (ref "IC8") (pin "9") (pinfunction "VDDQ(2)_9") (pintype "input"))
      (node (ref "JP1") (pin "2") (pinfunction "2_2") (pintype "passive"))
      (node (ref "JP1") (pin "4") (pinfunction "4_4") (pintype "passive"))
      (node (ref "JTAG1") (pin "6") (pinfunction "6_6") (pintype "passive"))
      (node (ref "OSC2") (pin "4") (pinfunction "VCC_4") (pintype "power_in"))
      (node (ref "U1") (pin "20") (pinfunction "VCC_20") (pintype "power_in"))
      (node (ref "U2") (pin "20") (pinfunction "VCC_20") (pintype "power_in"))
      (node (ref "U3") (pin "20") (pinfunction "VCC_20") (pintype "power_in"))
      (node (ref "U4") (pin "20") (pinfunction "VCC_20") (pintype "power_in"))
      (node (ref "XC95144XL") (pin "1") (pinfunction "VCCIO(1)_1") (pintype "input"))
      (node (ref "XC95144XL") (pin "109") (pinfunction "VCCIO(5)_109") (pintype "input"))
      (node (ref "XC95144XL") (pin "127") (pinfunction "VCCIO(6)_127") (pintype "input"))
      (node (ref "XC95144XL") (pin "141") (pinfunction "VCCINT(4)_141") (pintype "input"))
      (node (ref "XC95144XL") (pin "37") (pinfunction "VCCIO(2)_37") (pintype "input"))
      (node (ref "XC95144XL") (pin "42") (pinfunction "VCCINT(2)_42") (pintype "input"))
      (node (ref "XC95144XL") (pin "55") (pinfunction "VCCIO(3)_55") (pintype "input"))
      (node (ref "XC95144XL") (pin "73") (pinfunction "VCCIO(4)_73") (pintype "input"))
      (node (ref "XC95144XL") (pin "8") (pinfunction "VCCINT(1)_8") (pintype "input"))
      (node (ref "XC95144XL") (pin "84") (pinfunction "VCCINT(3)_84") (pintype "input"))
    )
    (net (code "205") (name "unconnected-(CONN1-17MHZ-PadPIN139)") (class "Default")
      (node (ref "CONN1") (pin "PIN139") (pinfunction "17MHZ_PIN139") (pintype "bidirectional"))
    )
    (net (code "206") (name "unconnected-(CONN1-AB-PadPIN168)") (class "Default")
      (node (ref "CONN1") (pin "PIN168") (pinfunction "AB_PIN168") (pintype "bidirectional"))
    )
    (net (code "207") (name "unconnected-(CONN1-AB_EXT-PadPIN167)") (class "Default")
      (node (ref "CONN1") (pin "PIN167") (pinfunction "AB_EXT_PIN167") (pintype "bidirectional"))
    )
    (net (code "208") (name "unconnected-(CONN1-AG-PadPIN166)") (class "Default")
      (node (ref "CONN1") (pin "PIN166") (pinfunction "AG_PIN166") (pintype "bidirectional"))
    )
    (net (code "209") (name "unconnected-(CONN1-AG_EXT-PadPIN165)") (class "Default")
      (node (ref "CONN1") (pin "PIN165") (pinfunction "AG_EXT_PIN165") (pintype "bidirectional"))
    )
    (net (code "210") (name "unconnected-(CONN1-AR-PadPIN164)") (class "Default")
      (node (ref "CONN1") (pin "PIN164") (pinfunction "AR_PIN164") (pintype "bidirectional"))
    )
    (net (code "211") (name "unconnected-(CONN1-AR_EXT-PadPIN163)") (class "Default")
      (node (ref "CONN1") (pin "PIN163") (pinfunction "AR_EXT_PIN163") (pintype "bidirectional"))
    )
    (net (code "212") (name "unconnected-(CONN1-CCK_B-PadPIN158)") (class "Default")
      (node (ref "CONN1") (pin "PIN158") (pinfunction "CCK_B_PIN158") (pintype "bidirectional"))
    )
    (net (code "213") (name "unconnected-(CONN1-CSYNC-PadPIN157)") (class "Default")
      (node (ref "CONN1") (pin "PIN157") (pinfunction "CSYNC_PIN157") (pintype "bidirectional"))
    )
    (net (code "214") (name "unconnected-(CONN1-DA_BCLK-PadPIN144)") (class "Default")
      (node (ref "CONN1") (pin "PIN144") (pinfunction "DA_BCLK_PIN144") (pintype "bidirectional"))
    )
    (net (code "215") (name "unconnected-(CONN1-DA_DATA-PadPIN141)") (class "Default")
      (node (ref "CONN1") (pin "PIN141") (pinfunction "DA_DATA_PIN141") (pintype "bidirectional"))
    )
    (net (code "216") (name "unconnected-(CONN1-DA_LRCLK-PadPIN143)") (class "Default")
      (node (ref "CONN1") (pin "PIN143") (pinfunction "DA_LRCLK_PIN143") (pintype "bidirectional"))
    )
    (net (code "217") (name "unconnected-(CONN1-DB-PadPIN149)") (class "Default")
      (node (ref "CONN1") (pin "PIN149") (pinfunction "DB_PIN149") (pintype "bidirectional"))
    )
    (net (code "218") (name "unconnected-(CONN1-DG-PadPIN148)") (class "Default")
      (node (ref "CONN1") (pin "PIN148") (pinfunction "DG_PIN148") (pintype "bidirectional"))
    )
    (net (code "219") (name "unconnected-(CONN1-DI-PadPIN150)") (class "Default")
      (node (ref "CONN1") (pin "PIN150") (pinfunction "DI_PIN150") (pintype "bidirectional"))
    )
    (net (code "220") (name "unconnected-(CONN1-DR-PadPIN147)") (class "Default")
      (node (ref "CONN1") (pin "PIN147") (pinfunction "DR_PIN147") (pintype "bidirectional"))
    )
    (net (code "221") (name "unconnected-(CONN1-HSYNC-PadPIN159)") (class "Default")
      (node (ref "CONN1") (pin "PIN159") (pinfunction "HSYNC_PIN159") (pintype "bidirectional"))
    )
    (net (code "222") (name "unconnected-(CONN1-IPEND-PadPIN84)") (class "Default")
      (node (ref "CONN1") (pin "PIN84") (pinfunction "IPEND_PIN84") (pintype "no_connect"))
    )
    (net (code "223") (name "unconnected-(CONN1-KB_CLOCK-PadPIN121)") (class "Default")
      (node (ref "CONN1") (pin "PIN121") (pinfunction "KB_CLOCK_PIN121") (pintype "bidirectional"))
    )
    (net (code "224") (name "unconnected-(CONN1-KB_DATA-PadPIN122)") (class "Default")
      (node (ref "CONN1") (pin "PIN122") (pinfunction "KB_DATA_PIN122") (pintype "bidirectional"))
    )
    (net (code "225") (name "unconnected-(CONN1-LEFT-PadPIN180)") (class "Default")
      (node (ref "CONN1") (pin "PIN180") (pinfunction "LEFT_PIN180") (pintype "bidirectional"))
    )
    (net (code "226") (name "unconnected-(CONN1-LEFT_EXT-PadPIN179)") (class "Default")
      (node (ref "CONN1") (pin "PIN179") (pinfunction "LEFT_EXT_PIN179") (pintype "bidirectional"))
    )
    (net (code "227") (name "unconnected-(CONN1-P$1-PadPIN1)") (class "Default")
      (node (ref "CONN1") (pin "PIN1") (pinfunction "P$1_PIN1") (pintype "no_connect"))
    )
    (net (code "228") (name "unconnected-(CONN1-P$2-PadPIN2)") (class "Default")
      (node (ref "CONN1") (pin "PIN2") (pinfunction "P$2_PIN2") (pintype "no_connect"))
    )
    (net (code "229") (name "unconnected-(CONN1-P$3-PadPIN3)") (class "Default")
      (node (ref "CONN1") (pin "PIN3") (pinfunction "P$3_PIN3") (pintype "no_connect"))
    )
    (net (code "230") (name "unconnected-(CONN1-P$4-PadPIN4)") (class "Default")
      (node (ref "CONN1") (pin "PIN4") (pinfunction "P$4_PIN4") (pintype "no_connect"))
    )
    (net (code "231") (name "unconnected-(CONN1-P$5-PadPIN5)") (class "Default")
      (node (ref "CONN1") (pin "PIN5") (pinfunction "P$5_PIN5") (pintype "no_connect"))
    )
    (net (code "232") (name "unconnected-(CONN1-P$6-PadPIN6)") (class "Default")
      (node (ref "CONN1") (pin "PIN6") (pinfunction "P$6_PIN6") (pintype "no_connect"))
    )
    (net (code "233") (name "unconnected-(CONN1-P$7-PadPIN7)") (class "Default")
      (node (ref "CONN1") (pin "PIN7") (pinfunction "P$7_PIN7") (pintype "no_connect"))
    )
    (net (code "234") (name "unconnected-(CONN1-P$8-PadPIN8)") (class "Default")
      (node (ref "CONN1") (pin "PIN8") (pinfunction "P$8_PIN8") (pintype "no_connect"))
    )
    (net (code "235") (name "unconnected-(CONN1-P$95-PadPIN95)") (class "Default")
      (node (ref "CONN1") (pin "PIN95") (pinfunction "P$95_PIN95") (pintype "no_connect"))
    )
    (net (code "236") (name "unconnected-(CONN1-P$100-PadPIN100)") (class "Default")
      (node (ref "CONN1") (pin "PIN100") (pinfunction "P$100_PIN100") (pintype "no_connect"))
    )
    (net (code "237") (name "unconnected-(CONN1-P$106-PadPIN106)") (class "Default")
      (node (ref "CONN1") (pin "PIN106") (pinfunction "P$106_PIN106") (pintype "no_connect"))
    )
    (net (code "238") (name "unconnected-(CONN1-P$107-PadPIN107)") (class "Default")
      (node (ref "CONN1") (pin "PIN107") (pinfunction "P$107_PIN107") (pintype "no_connect"))
    )
    (net (code "239") (name "unconnected-(CONN1-P$108-PadPIN108)") (class "Default")
      (node (ref "CONN1") (pin "PIN108") (pinfunction "P$108_PIN108") (pintype "no_connect"))
    )
    (net (code "240") (name "unconnected-(CONN1-P$109-PadPIN109)") (class "Default")
      (node (ref "CONN1") (pin "PIN109") (pinfunction "P$109_PIN109") (pintype "no_connect"))
    )
    (net (code "241") (name "unconnected-(CONN1-P$110-PadPIN110)") (class "Default")
      (node (ref "CONN1") (pin "PIN110") (pinfunction "P$110_PIN110") (pintype "no_connect"))
    )
    (net (code "242") (name "unconnected-(CONN1-PIXELCLK-PadPIN154)") (class "Default")
      (node (ref "CONN1") (pin "PIN154") (pinfunction "PIXELCLK_PIN154") (pintype "bidirectional"))
    )
    (net (code "243") (name "unconnected-(CONN1-RIGHT-PadPIN182)") (class "Default")
      (node (ref "CONN1") (pin "PIN182") (pinfunction "RIGHT_PIN182") (pintype "bidirectional"))
    )
    (net (code "244") (name "unconnected-(CONN1-RIGHT_EXT-PadPIN181)") (class "Default")
      (node (ref "CONN1") (pin "PIN181") (pinfunction "RIGHT_EXT_PIN181") (pintype "bidirectional"))
    )
    (net (code "245") (name "unconnected-(CONN1-SYSTEM-PadPIN131)") (class "Default")
      (node (ref "CONN1") (pin "PIN131") (pinfunction "SYSTEM_PIN131") (pintype "bidirectional"))
    )
    (net (code "246") (name "unconnected-(CONN1-VSYNC-PadPIN160)") (class "Default")
      (node (ref "CONN1") (pin "PIN160") (pinfunction "VSYNC_PIN160") (pintype "bidirectional"))
    )
    (net (code "247") (name "unconnected-(CONN1-XCLK-PadPIN173)") (class "Default")
      (node (ref "CONN1") (pin "PIN173") (pinfunction "XCLK_PIN173") (pintype "bidirectional"))
    )
    (net (code "248") (name "unconnected-(CONN1-~{BLANK}-PadPIN153)") (class "Default")
      (node (ref "CONN1") (pin "PIN153") (pinfunction "~{BLANK}_PIN153") (pintype "bidirectional"))
    )
    (net (code "249") (name "unconnected-(CONN1-~{CPU_BGACK}-PadPIN115)") (class "Default")
      (node (ref "CONN1") (pin "PIN115") (pinfunction "~{CPU_BGACK}_PIN115") (pintype "bidirectional"))
    )
    (net (code "250") (name "unconnected-(CONN1-~{DKRD}-PadPIN129)") (class "Default")
      (node (ref "CONN1") (pin "PIN129") (pinfunction "~{DKRD}_PIN129") (pintype "bidirectional"))
    )
    (net (code "251") (name "unconnected-(CONN1-~{DKWD}-PadPIN130)") (class "Default")
      (node (ref "CONN1") (pin "PIN130") (pinfunction "~{DKWD}_PIN130") (pintype "bidirectional"))
    )
    (net (code "252") (name "unconnected-(CONN1-~{DKWE}-PadPIN132)") (class "Default")
      (node (ref "CONN1") (pin "PIN132") (pinfunction "~{DKWE}_PIN132") (pintype "bidirectional"))
    )
    (net (code "253") (name "unconnected-(CONN1-~{ECS}-PadPIN87)") (class "Default")
      (node (ref "CONN1") (pin "PIN87") (pinfunction "~{ECS}_PIN87") (pintype "bidirectional"))
    )
    (net (code "254") (name "unconnected-(CONN1-~{EXP_BGACK}-PadPIN116)") (class "Default")
      (node (ref "CONN1") (pin "PIN116") (pinfunction "~{EXP_BGACK}_PIN116") (pintype "bidirectional"))
    )
    (net (code "255") (name "unconnected-(CONN1-~{EXT_AUDIO}-PadPIN140)") (class "Default")
      (node (ref "CONN1") (pin "PIN140") (pinfunction "~{EXT_AUDIO}_PIN140") (pintype "bidirectional"))
    )
    (net (code "256") (name "unconnected-(CONN1-~{EXT_VIDEO}-PadPIN174)") (class "Default")
      (node (ref "CONN1") (pin "PIN174") (pinfunction "~{EXT_VIDEO}_PIN174") (pintype "bidirectional"))
    )
    (net (code "257") (name "unconnected-(CONN1-~{HALT}-PadPIN86)") (class "Default")
      (node (ref "CONN1") (pin "PIN86") (pinfunction "~{HALT}_PIN86") (pintype "bidirectional"))
    )
    (net (code "258") (name "unconnected-(CONN1-~{LED}-PadPIN125)") (class "Default")
      (node (ref "CONN1") (pin "PIN125") (pinfunction "~{LED}_PIN125") (pintype "bidirectional"))
    )
    (net (code "259") (name "unconnected-(CONN1-~{MUTE}-PadPIN142)") (class "Default")
      (node (ref "CONN1") (pin "PIN142") (pinfunction "~{MUTE}_PIN142") (pintype "bidirectional"))
    )
    (net (code "260") (name "unconnected-(CONN1-~{NTSC}-PadPIN171)") (class "Default")
      (node (ref "CONN1") (pin "PIN171") (pinfunction "~{NTSC}_PIN171") (pintype "bidirectional"))
    )
    (net (code "261") (name "unconnected-(CONN1-~{OCS}-PadPIN88)") (class "Default")
      (node (ref "CONN1") (pin "PIN88") (pinfunction "~{OCS}_PIN88") (pintype "bidirectional"))
    )
    (net (code "262") (name "unconnected-(CONN1-~{PIXELSW_EXT}-PadPIN151)") (class "Default")
      (node (ref "CONN1") (pin "PIN151") (pinfunction "~{PIXELSW_EXT}_PIN151") (pintype "bidirectional"))
    )
    (net (code "263") (name "unconnected-(CONN1-~{PIXELSW}-PadPIN152)") (class "Default")
      (node (ref "CONN1") (pin "PIN152") (pinfunction "~{PIXELSW}_PIN152") (pintype "bidirectional"))
    )
    (net (code "264") (name "unconnected-(CONN1-~{XCLKEN}-PadPIN172)") (class "Default")
      (node (ref "CONN1") (pin "PIN172") (pinfunction "~{XCLKEN}_PIN172") (pintype "bidirectional"))
    )
    (net (code "265") (name "unconnected-(ESPHEADER-Pad3)") (class "Default")
      (node (ref "ESPHEADER") (pin "3") (pinfunction "3_3") (pintype "passive"))
    )
    (net (code "266") (name "unconnected-(ESPHEADER-Pad4)") (class "Default")
      (node (ref "ESPHEADER") (pin "4") (pinfunction "4_4") (pintype "passive"))
    )
    (net (code "267") (name "unconnected-(ESPHEADER-Pad5)") (class "Default")
      (node (ref "ESPHEADER") (pin "5") (pinfunction "5_5") (pintype "passive"))
    )
    (net (code "268") (name "unconnected-(IC1A-ECS-PadM02)") (class "Default")
      (node (ref "IC1") (pin "M02") (pinfunction "ECS_M02") (pintype "output"))
    )
    (net (code "269") (name "unconnected-(IC1A-IPEND-PadE13)") (class "Default")
      (node (ref "IC1") (pin "E13") (pinfunction "IPEND_E13") (pintype "output"))
    )
    (net (code "270") (name "unconnected-(IC1A-OCS-PadD03)") (class "Default")
      (node (ref "IC1") (pin "D03") (pinfunction "OCS_D03") (pintype "output"))
    )
    (net (code "271") (name "unconnected-(IC1A-RMC-PadB01)") (class "Default")
      (node (ref "IC1") (pin "B01") (pinfunction "RMC_B01") (pintype "output"))
    )
    (net (code "272") (name "unconnected-(IC7-NC-Pad40)") (class "Default")
      (node (ref "IC7") (pin "40") (pinfunction "NC_40") (pintype "input"))
    )
    (net (code "273") (name "unconnected-(IC8-NC-Pad40)") (class "Default")
      (node (ref "IC8") (pin "40") (pinfunction "NC_40") (pintype "input"))
    )
    (net (code "274") (name "unconnected-(IDEAB-S-Pad34)") (class "Default")
      (node (ref "IDE") (pin "34") (pinfunction "S_34") (pintype "passive"))
    )
    (net (code "275") (name "unconnected-(IDEM-S-Pad20)") (class "Default")
      (node (ref "IDE") (pin "20") (pinfunction "S_20") (pintype "passive"))
    )
    (net (code "276") (name "unconnected-(IDEN-S-Pad21)") (class "Default")
      (node (ref "IDE") (pin "21") (pinfunction "S_21") (pintype "passive"))
    )
    (net (code "277") (name "unconnected-(IDEU-S-Pad28)") (class "Default")
      (node (ref "IDE") (pin "28") (pinfunction "S_28") (pintype "passive"))
    )
    (net (code "278") (name "unconnected-(IDEV-S-Pad29)") (class "Default")
      (node (ref "IDE") (pin "29") (pinfunction "S_29") (pintype "passive"))
    )
    (net (code "279") (name "unconnected-(IDEZ-S-Pad32)") (class "Default")
      (node (ref "IDE") (pin "32") (pinfunction "S_32") (pintype "passive"))
    )
    (net (code "280") (name "unconnected-(OSC2-INH-Pad1)") (class "Default")
      (node (ref "OSC2") (pin "1") (pinfunction "INH_1") (pintype "bidirectional"))
    )
    (net (code "281") (name "unconnected-(RN2-Pad2)") (class "Default")
      (node (ref "RN2") (pin "2") (pinfunction "2_2") (pintype "passive"))
    )
    (net (code "282") (name "unconnected-(RN2-Pad3)") (class "Default")
      (node (ref "RN2") (pin "3") (pinfunction "3_3") (pintype "passive"))
    )
    (net (code "283") (name "unconnected-(U1-NC-Pad1)") (class "Default")
      (node (ref "U1") (pin "1") (pinfunction "NC_1") (pintype "no_connect"))
    )
    (net (code "284") (name "unconnected-(U2-NC-Pad1)") (class "Default")
      (node (ref "U2") (pin "1") (pinfunction "NC_1") (pintype "no_connect"))
    )
    (net (code "285") (name "unconnected-(U3-NC-Pad1)") (class "Default")
      (node (ref "U3") (pin "1") (pinfunction "NC_1") (pintype "no_connect"))
    )
    (net (code "286") (name "unconnected-(U4-NC-Pad1)") (class "Default")
      (node (ref "U4") (pin "1") (pinfunction "NC_1") (pintype "no_connect"))
    )
    (net (code "287") (name "unconnected-(XC95144XL-PB4{slash}6-Pad129)") (class "Default")
      (node (ref "XC95144XL") (pin "129") (pinfunction "PB4/6_129") (pintype "input"))
    )
    (net (code "288") (name "unconnected-(XC95144XL-PB4{slash}8-Pad130)") (class "Default")
      (node (ref "XC95144XL") (pin "130") (pinfunction "PB4/8_130") (pintype "input"))
    )
    (net (code "289") (name "unconnected-(XC95144XL-PB4{slash}9-Pad131)") (class "Default")
      (node (ref "XC95144XL") (pin "131") (pinfunction "PB4/9_131") (pintype "input"))
    )
  )
)
